# zx_kit2.net
KiCad netlist of a schematic drawn in EAGLE
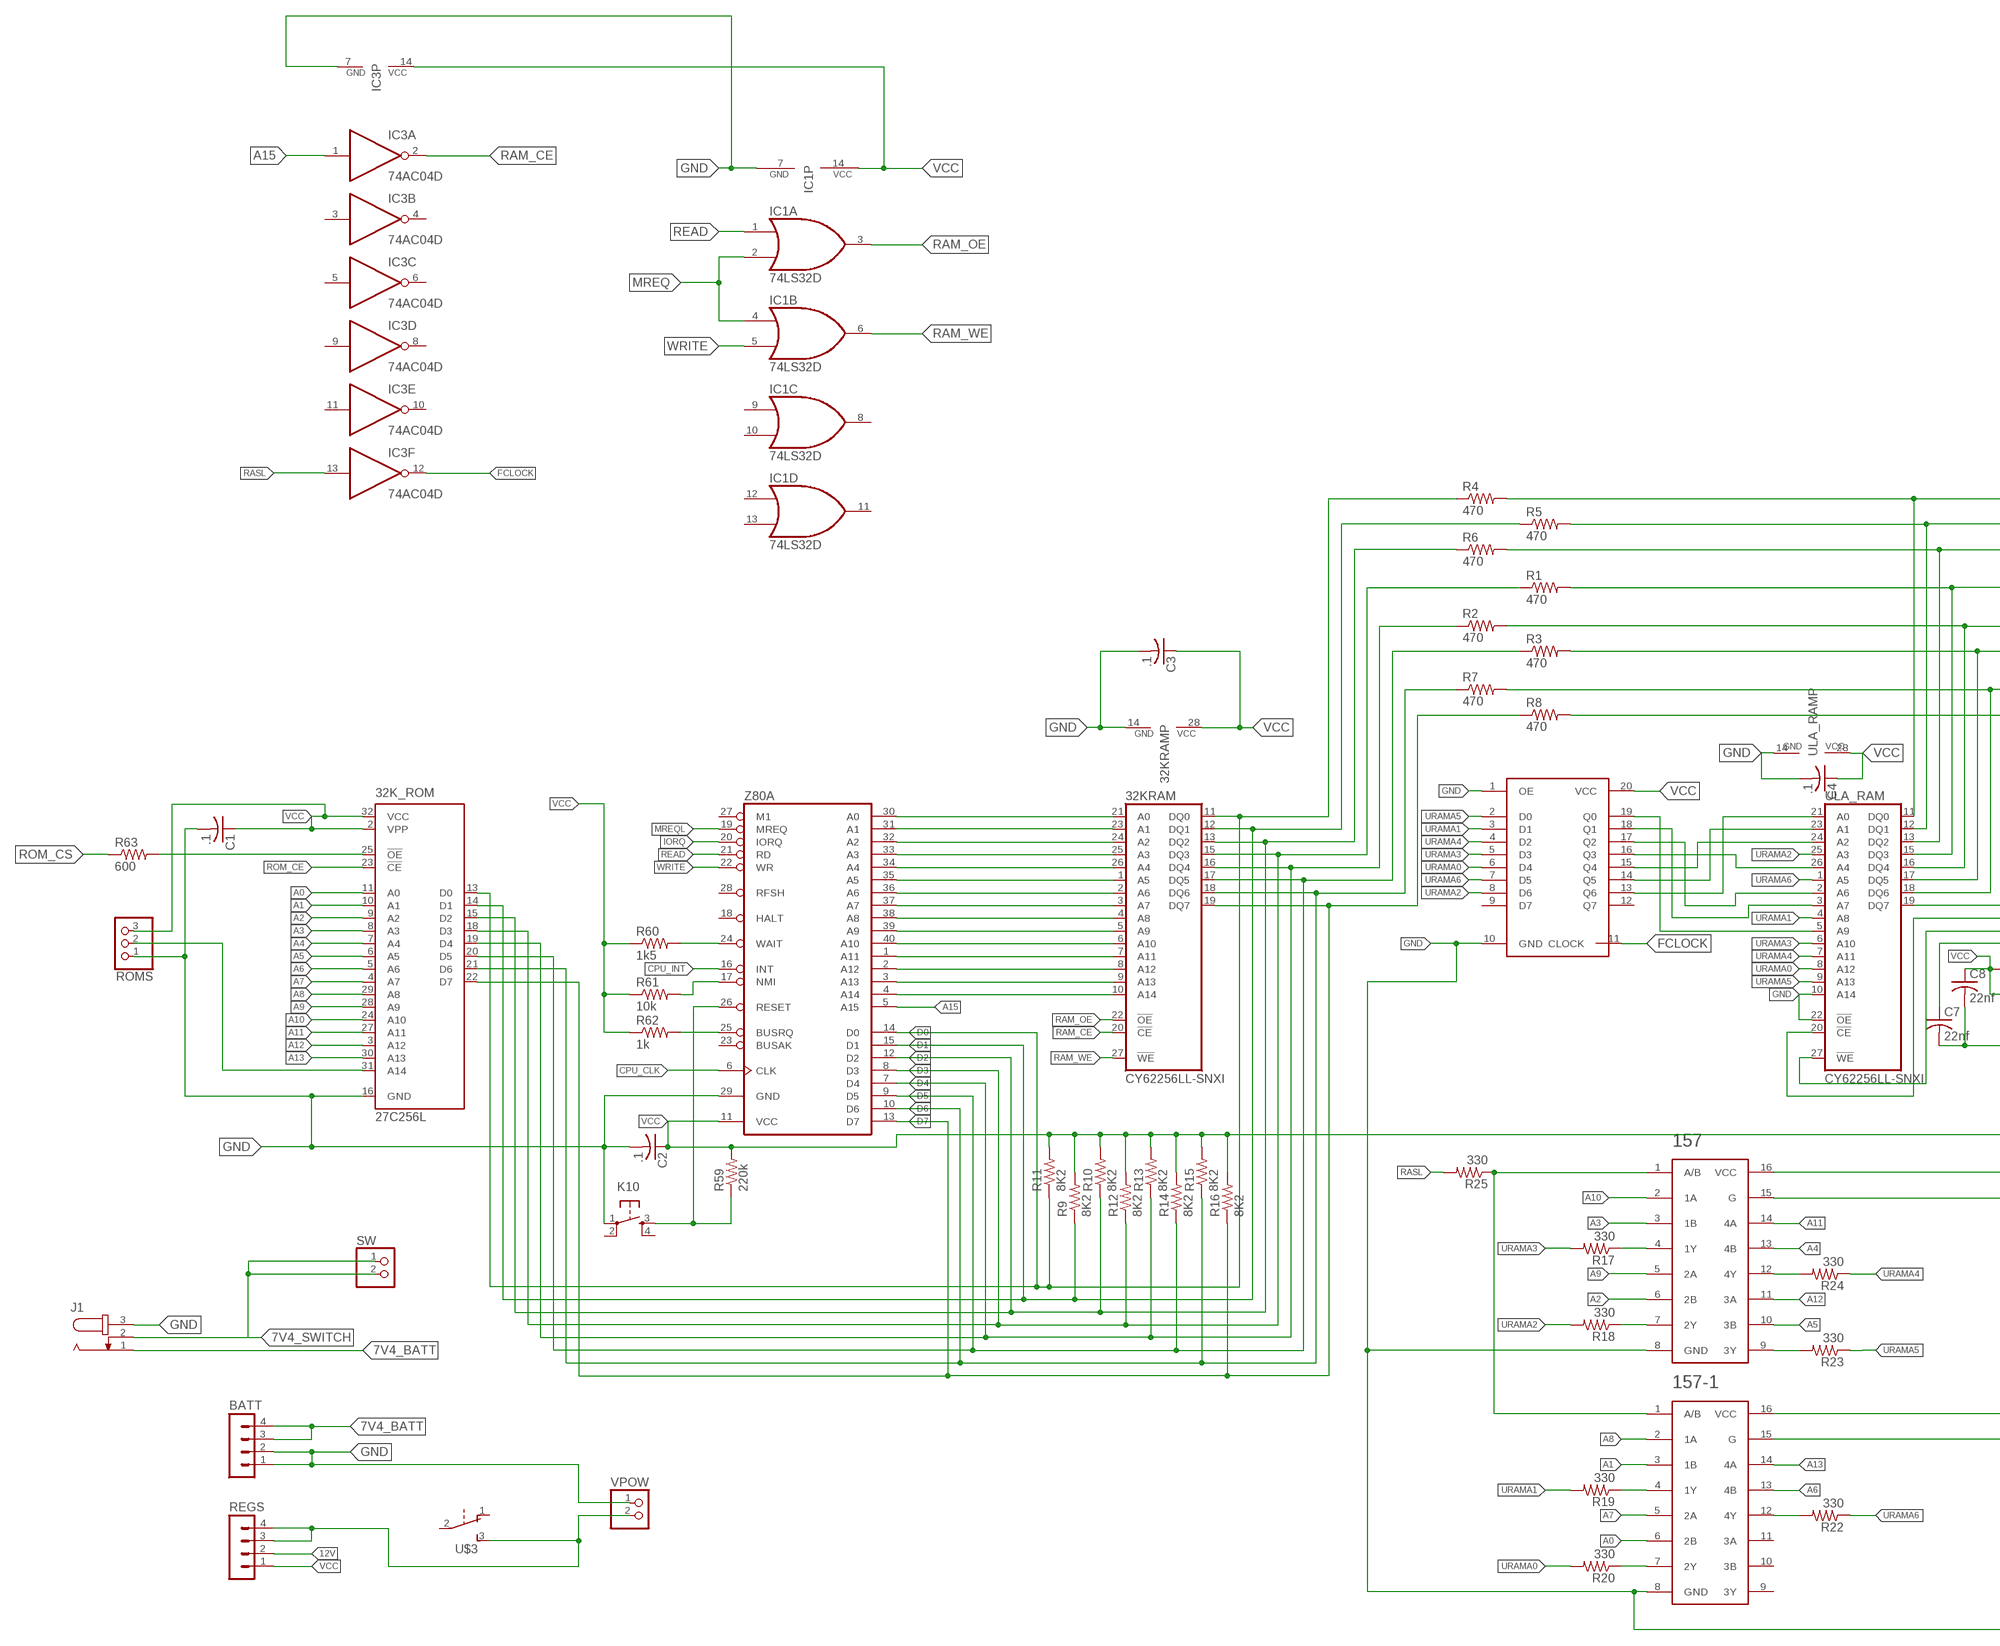
[diagram p0: schematic, sheet 1, part 1 of 3]
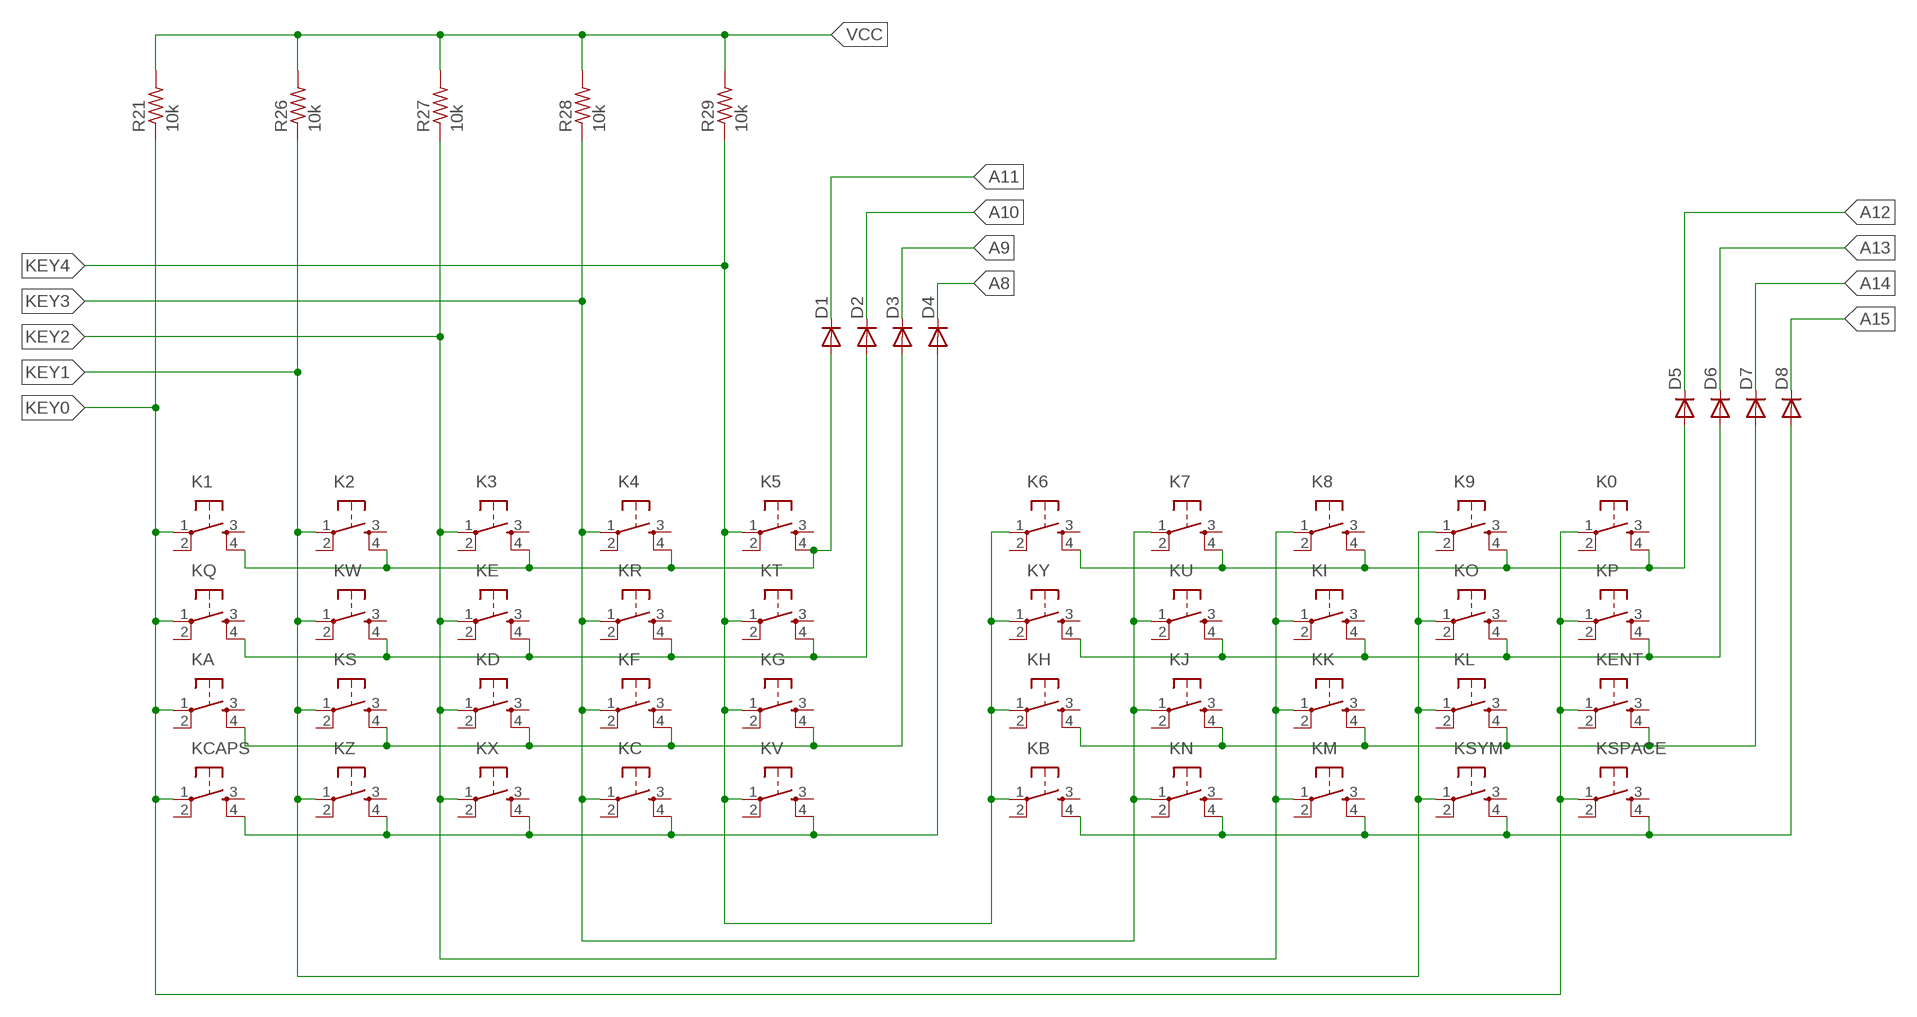
[diagram p1: schematic, sheet 1, part 2 of 3]
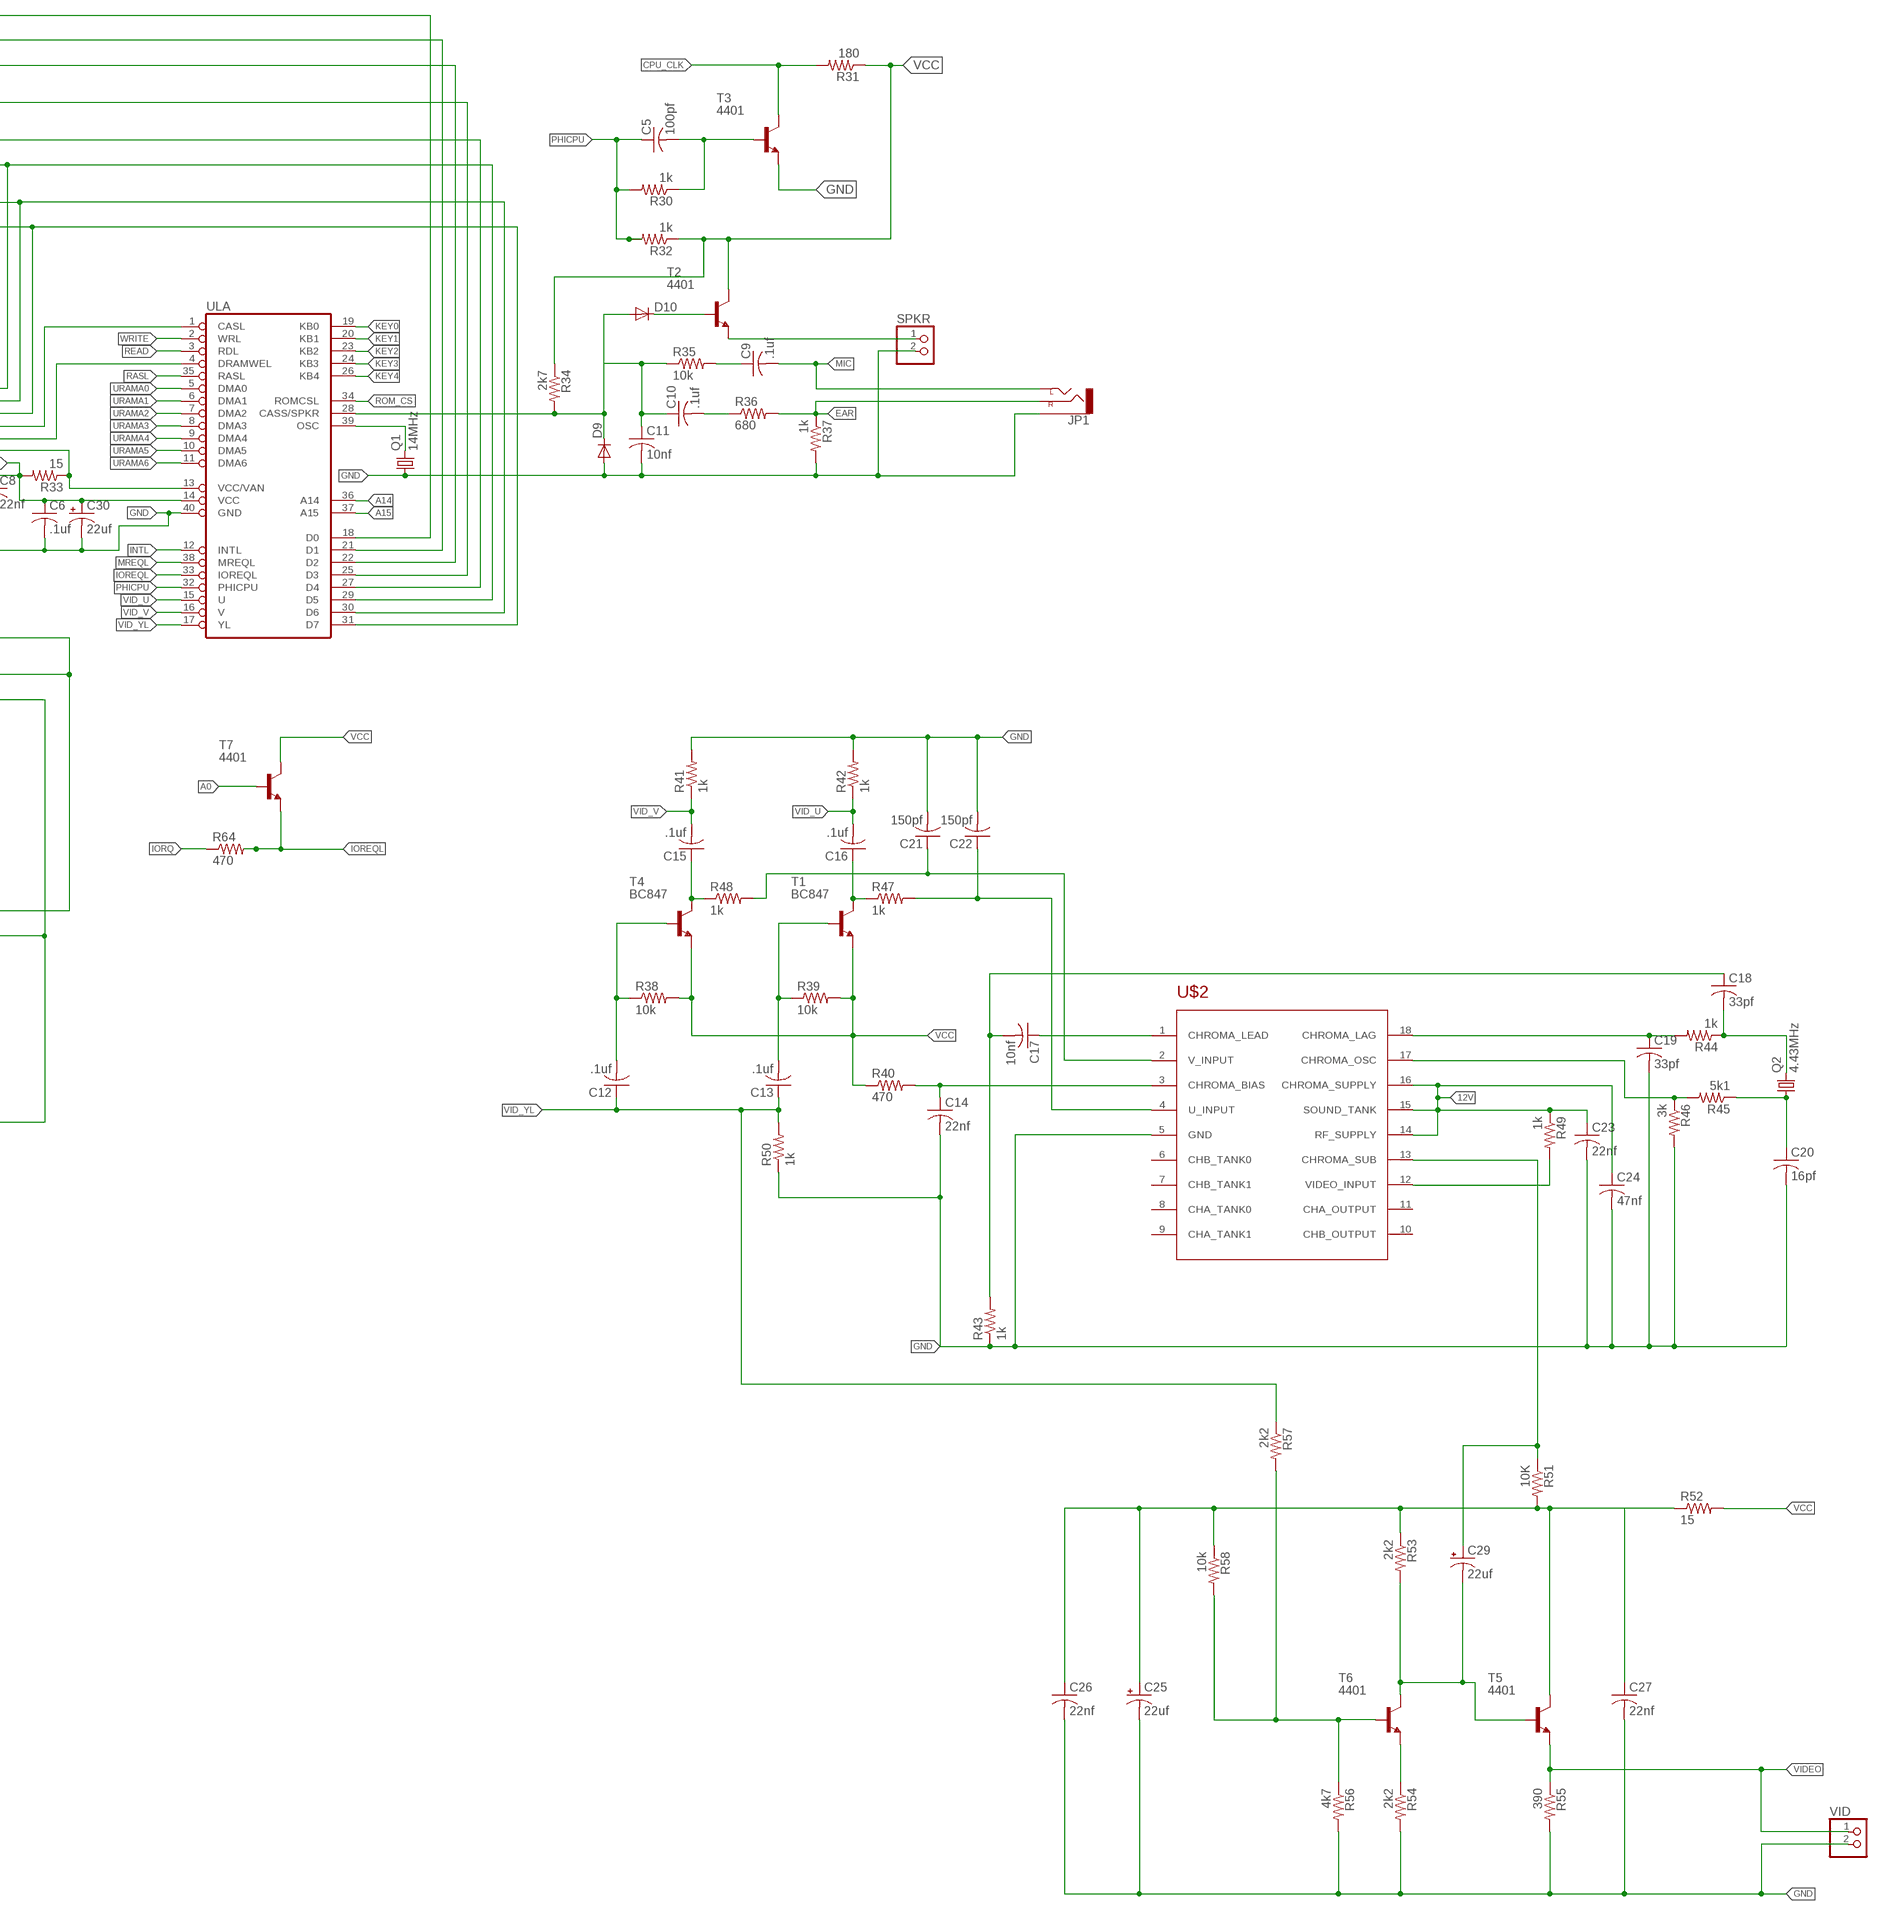
[diagram p2: schematic, sheet 1, part 3 of 3]

(export (version "E")
  (design (tool "Eeschema 10.0.6"))
  (components
    (comp (ref "32KRAM")
      (value "CY62256LL-SNXI")
      (footprint "eagle-import:SOJ28_3")
      (libsource (lib "eagle-import") (part "CY62256LL-?SNXI"))
    )
    (comp (ref "32K_ROM")
      (value "27C256L")
      (footprint "eagle-import:PLCC-32")
      (fields (field (name "MPN") "AT27C256R-70JU"))
      (libsource (lib "eagle-import") (part "27256LC"))
    )
    (comp (ref "157")
      (value "SN74HC157D")
      (footprint "eagle-import:SO16")
      (libsource (lib "eagle-import") (part "SN74HC157D"))
    )
    (comp (ref "157-1")
      (value "SN74HC157D")
      (footprint "eagle-import:SO16")
      (libsource (lib "eagle-import") (part "SN74HC157D"))
    )
    (comp (ref "BATT")
      (value "MA04-1")
      (footprint "eagle-import:MA04-1")
      (libsource (lib "eagle-import") (part "MA04-1"))
    )
    (comp (ref "C1")
      (value ".1")
      (footprint "eagle-import:C0805")
      (libsource (lib "eagle-import") (part "resistor_C-USC0805"))
    )
    (comp (ref "C2")
      (value ".1")
      (footprint "eagle-import:C0805")
      (libsource (lib "eagle-import") (part "resistor_C-USC0805"))
    )
    (comp (ref "C3")
      (value ".1")
      (footprint "eagle-import:C0805")
      (libsource (lib "eagle-import") (part "resistor_C-USC0805"))
    )
    (comp (ref "C4")
      (value ".1")
      (footprint "eagle-import:C0805")
      (libsource (lib "eagle-import") (part "resistor_C-USC0805"))
    )
    (comp (ref "C5")
      (value "100pf")
      (footprint "eagle-import:C0805")
      (libsource (lib "eagle-import") (part "C-USC0805"))
    )
    (comp (ref "C6")
      (value ".1uf")
      (footprint "eagle-import:C0805")
      (libsource (lib "eagle-import") (part "C-USC0805"))
    )
    (comp (ref "C7")
      (value "22nf")
      (footprint "eagle-import:C0805")
      (libsource (lib "eagle-import") (part "C-USC0805"))
    )
    (comp (ref "C8")
      (value "22nf")
      (footprint "eagle-import:C0805")
      (libsource (lib "eagle-import") (part "C-USC0805"))
    )
    (comp (ref "C9")
      (value ".1uf")
      (footprint "eagle-import:C0805")
      (libsource (lib "eagle-import") (part "C-USC0805"))
    )
    (comp (ref "C10")
      (value ".1uf")
      (footprint "eagle-import:C0805")
      (libsource (lib "eagle-import") (part "C-USC0805"))
    )
    (comp (ref "C11")
      (value "10nf")
      (footprint "eagle-import:C0805")
      (libsource (lib "eagle-import") (part "C-USC0805"))
    )
    (comp (ref "C12")
      (value ".1uf")
      (footprint "eagle-import:C0805")
      (libsource (lib "eagle-import") (part "C-USC0805"))
    )
    (comp (ref "C13")
      (value ".1uf")
      (footprint "eagle-import:C0805")
      (libsource (lib "eagle-import") (part "C-USC0805"))
    )
    (comp (ref "C14")
      (value "22nf")
      (footprint "eagle-import:C0805")
      (libsource (lib "eagle-import") (part "C-USC0805"))
    )
    (comp (ref "C15")
      (value ".1uf")
      (footprint "eagle-import:C0805")
      (libsource (lib "eagle-import") (part "C-USC0805"))
    )
    (comp (ref "C16")
      (value ".1uf")
      (footprint "eagle-import:C0805")
      (libsource (lib "eagle-import") (part "C-USC0805"))
    )
    (comp (ref "C17")
      (value "10nf")
      (footprint "eagle-import:C0805")
      (libsource (lib "eagle-import") (part "C-USC0805"))
    )
    (comp (ref "C18")
      (value "33pf")
      (footprint "eagle-import:C0805")
      (libsource (lib "eagle-import") (part "C-USC0805"))
    )
    (comp (ref "C19")
      (value "33pf")
      (footprint "eagle-import:C0805")
      (libsource (lib "eagle-import") (part "C-USC0805"))
    )
    (comp (ref "C20")
      (value "16pf")
      (footprint "eagle-import:C0805")
      (libsource (lib "eagle-import") (part "C-USC0805"))
    )
    (comp (ref "C21")
      (value "150pf")
      (footprint "eagle-import:C0805")
      (libsource (lib "eagle-import") (part "C-USC0805"))
    )
    (comp (ref "C22")
      (value "150pf")
      (footprint "eagle-import:C0805")
      (libsource (lib "eagle-import") (part "C-USC0805"))
    )
    (comp (ref "C23")
      (value "22nf")
      (footprint "eagle-import:C0805")
      (libsource (lib "eagle-import") (part "C-USC0805"))
    )
    (comp (ref "C24")
      (value "47nf")
      (footprint "eagle-import:C0805")
      (libsource (lib "eagle-import") (part "C-USC0805"))
    )
    (comp (ref "C25")
      (value "22uf")
      (footprint "eagle-import:PANASONIC_B")
      (libsource (lib "eagle-import") (part "CPOL-USB"))
    )
    (comp (ref "C26")
      (value "22nf")
      (footprint "eagle-import:C0805")
      (libsource (lib "eagle-import") (part "C-USC0805"))
    )
    (comp (ref "C27")
      (value "22nf")
      (footprint "eagle-import:C0805")
      (libsource (lib "eagle-import") (part "C-USC0805"))
    )
    (comp (ref "C29")
      (value "22uf")
      (footprint "eagle-import:PANASONIC_B")
      (libsource (lib "eagle-import") (part "CPOL-USB"))
    )
    (comp (ref "C30")
      (value "22uf")
      (footprint "eagle-import:PANASONIC_B")
      (libsource (lib "eagle-import") (part "CPOL-USB"))
    )
    (comp (ref "D1")
      (value "DIODE-SOD123")
      (footprint "eagle-import:SOD123")
      (libsource (lib "eagle-import") (part "DIODE-SOD123"))
    )
    (comp (ref "D2")
      (value "DIODE-SOD123")
      (footprint "eagle-import:SOD123")
      (libsource (lib "eagle-import") (part "DIODE-SOD123"))
    )
    (comp (ref "D3")
      (value "DIODE-SOD123")
      (footprint "eagle-import:SOD123")
      (libsource (lib "eagle-import") (part "DIODE-SOD123"))
    )
    (comp (ref "D4")
      (value "DIODE-SOD123")
      (footprint "eagle-import:SOD123")
      (libsource (lib "eagle-import") (part "DIODE-SOD123"))
    )
    (comp (ref "D5")
      (value "DIODE-SOD123")
      (footprint "eagle-import:SOD123")
      (libsource (lib "eagle-import") (part "DIODE-SOD123"))
    )
    (comp (ref "D6")
      (value "DIODE-SOD123")
      (footprint "eagle-import:SOD123")
      (libsource (lib "eagle-import") (part "DIODE-SOD123"))
    )
    (comp (ref "D7")
      (value "DIODE-SOD123")
      (footprint "eagle-import:SOD123")
      (libsource (lib "eagle-import") (part "DIODE-SOD123"))
    )
    (comp (ref "D8")
      (value "DIODE-SOD123")
      (footprint "eagle-import:SOD123")
      (libsource (lib "eagle-import") (part "DIODE-SOD123"))
    )
    (comp (ref "D9")
      (value "DIODE-SOD123")
      (footprint "eagle-import:SOD123")
      (libsource (lib "eagle-import") (part "DIODE-SOD123"))
    )
    (comp (ref "D10")
      (value "DIODE-SOD123")
      (footprint "eagle-import:SOD123")
      (libsource (lib "eagle-import") (part "DIODE-SOD123"))
    )
    (comp (ref "IC1")
      (value "74LS32D")
      (footprint "eagle-import:SO14")
      (libsource (lib "eagle-import") (part "7432DLS"))
    )
    (comp (ref "IC3")
      (value "74AC04D")
      (footprint "eagle-import:SO14")
      (libsource (lib "eagle-import") (part "7404DAC"))
    )
    (comp (ref "J1")
      (value "JACK-PLUG0")
      (footprint "eagle-import:SPC4077")
      (libsource (lib "eagle-import") (part "JACK-PLUG0"))
    )
    (comp (ref "JP1")
      (value "AUDIO-JACKPTH")
      (footprint "eagle-import:AUDIO-JACK")
      (libsource (lib "eagle-import") (part "AUDIO-JACKPTH"))
    )
    (comp (ref "K0")
      (value "DTS-6")
      (footprint "eagle-import:DTS-6")
      (libsource (lib "eagle-import") (part "DTS-6"))
    )
    (comp (ref "K1")
      (value "DTS-6")
      (footprint "eagle-import:DTS-6")
      (libsource (lib "eagle-import") (part "DTS-6"))
    )
    (comp (ref "K2")
      (value "DTS-6")
      (footprint "eagle-import:DTS-6")
      (libsource (lib "eagle-import") (part "DTS-6"))
    )
    (comp (ref "K3")
      (value "DTS-6")
      (footprint "eagle-import:DTS-6")
      (libsource (lib "eagle-import") (part "DTS-6"))
    )
    (comp (ref "K4")
      (value "DTS-6")
      (footprint "eagle-import:DTS-6")
      (libsource (lib "eagle-import") (part "DTS-6"))
    )
    (comp (ref "K5")
      (value "DTS-6")
      (footprint "eagle-import:DTS-6")
      (libsource (lib "eagle-import") (part "DTS-6"))
    )
    (comp (ref "K6")
      (value "DTS-6")
      (footprint "eagle-import:DTS-6")
      (libsource (lib "eagle-import") (part "DTS-6"))
    )
    (comp (ref "K7")
      (value "DTS-6")
      (footprint "eagle-import:DTS-6")
      (libsource (lib "eagle-import") (part "DTS-6"))
    )
    (comp (ref "K8")
      (value "DTS-6")
      (footprint "eagle-import:DTS-6")
      (libsource (lib "eagle-import") (part "DTS-6"))
    )
    (comp (ref "K9")
      (value "DTS-6")
      (footprint "eagle-import:DTS-6")
      (libsource (lib "eagle-import") (part "DTS-6"))
    )
    (comp (ref "K10")
      (value "DTS-6")
      (footprint "eagle-import:DTS-6")
      (libsource (lib "eagle-import") (part "DTS-6"))
    )
    (comp (ref "KA")
      (value "DTS-6")
      (footprint "eagle-import:DTS-6")
      (libsource (lib "eagle-import") (part "DTS-6"))
    )
    (comp (ref "KB")
      (value "DTS-6")
      (footprint "eagle-import:DTS-6")
      (libsource (lib "eagle-import") (part "DTS-6"))
    )
    (comp (ref "KC")
      (value "DTS-6")
      (footprint "eagle-import:DTS-6")
      (libsource (lib "eagle-import") (part "DTS-6"))
    )
    (comp (ref "KCAPS")
      (value "DTS-6")
      (footprint "eagle-import:DTS-6")
      (libsource (lib "eagle-import") (part "DTS-6"))
    )
    (comp (ref "KD")
      (value "DTS-6")
      (footprint "eagle-import:DTS-6")
      (libsource (lib "eagle-import") (part "DTS-6"))
    )
    (comp (ref "KE")
      (value "DTS-6")
      (footprint "eagle-import:DTS-6")
      (libsource (lib "eagle-import") (part "DTS-6"))
    )
    (comp (ref "KENT")
      (value "DTS-6")
      (footprint "eagle-import:DTS-6")
      (libsource (lib "eagle-import") (part "DTS-6"))
    )
    (comp (ref "KF")
      (value "DTS-6")
      (footprint "eagle-import:DTS-6")
      (libsource (lib "eagle-import") (part "DTS-6"))
    )
    (comp (ref "KG")
      (value "DTS-6")
      (footprint "eagle-import:DTS-6")
      (libsource (lib "eagle-import") (part "DTS-6"))
    )
    (comp (ref "KH")
      (value "DTS-6")
      (footprint "eagle-import:DTS-6")
      (libsource (lib "eagle-import") (part "DTS-6"))
    )
    (comp (ref "KI")
      (value "DTS-6")
      (footprint "eagle-import:DTS-6")
      (libsource (lib "eagle-import") (part "DTS-6"))
    )
    (comp (ref "KJ")
      (value "DTS-6")
      (footprint "eagle-import:DTS-6")
      (libsource (lib "eagle-import") (part "DTS-6"))
    )
    (comp (ref "KK")
      (value "DTS-6")
      (footprint "eagle-import:DTS-6")
      (libsource (lib "eagle-import") (part "DTS-6"))
    )
    (comp (ref "KL")
      (value "DTS-6")
      (footprint "eagle-import:DTS-6")
      (libsource (lib "eagle-import") (part "DTS-6"))
    )
    (comp (ref "KM")
      (value "DTS-6")
      (footprint "eagle-import:DTS-6")
      (libsource (lib "eagle-import") (part "DTS-6"))
    )
    (comp (ref "KN")
      (value "DTS-6")
      (footprint "eagle-import:DTS-6")
      (libsource (lib "eagle-import") (part "DTS-6"))
    )
    (comp (ref "KO")
      (value "DTS-6")
      (footprint "eagle-import:DTS-6")
      (libsource (lib "eagle-import") (part "DTS-6"))
    )
    (comp (ref "KP")
      (value "DTS-6")
      (footprint "eagle-import:DTS-6")
      (libsource (lib "eagle-import") (part "DTS-6"))
    )
    (comp (ref "KQ")
      (value "DTS-6")
      (footprint "eagle-import:DTS-6")
      (libsource (lib "eagle-import") (part "DTS-6"))
    )
    (comp (ref "KR")
      (value "DTS-6")
      (footprint "eagle-import:DTS-6")
      (libsource (lib "eagle-import") (part "DTS-6"))
    )
    (comp (ref "KS")
      (value "DTS-6")
      (footprint "eagle-import:DTS-6")
      (libsource (lib "eagle-import") (part "DTS-6"))
    )
    (comp (ref "KSPACE")
      (value "DTS-6")
      (footprint "eagle-import:DTS-6")
      (libsource (lib "eagle-import") (part "DTS-6"))
    )
    (comp (ref "KSYM")
      (value "DTS-6")
      (footprint "eagle-import:DTS-6")
      (libsource (lib "eagle-import") (part "DTS-6"))
    )
    (comp (ref "KT")
      (value "DTS-6")
      (footprint "eagle-import:DTS-6")
      (libsource (lib "eagle-import") (part "DTS-6"))
    )
    (comp (ref "KU")
      (value "DTS-6")
      (footprint "eagle-import:DTS-6")
      (libsource (lib "eagle-import") (part "DTS-6"))
    )
    (comp (ref "KV")
      (value "DTS-6")
      (footprint "eagle-import:DTS-6")
      (libsource (lib "eagle-import") (part "DTS-6"))
    )
    (comp (ref "KW")
      (value "DTS-6")
      (footprint "eagle-import:DTS-6")
      (libsource (lib "eagle-import") (part "DTS-6"))
    )
    (comp (ref "KX")
      (value "DTS-6")
      (footprint "eagle-import:DTS-6")
      (libsource (lib "eagle-import") (part "DTS-6"))
    )
    (comp (ref "KY")
      (value "DTS-6")
      (footprint "eagle-import:DTS-6")
      (libsource (lib "eagle-import") (part "DTS-6"))
    )
    (comp (ref "KZ")
      (value "DTS-6")
      (footprint "eagle-import:DTS-6")
      (libsource (lib "eagle-import") (part "DTS-6"))
    )
    (comp (ref "Q1")
      (value "14MHz")
      (footprint "eagle-import:CTS406")
      (libsource (lib "eagle-import") (part "CRYSTALCTS406"))
    )
    (comp (ref "Q2")
      (value "4.43MHz")
      (footprint "eagle-import:HC49_S")
      (libsource (lib "eagle-import") (part "CRYSTALHC49S"))
    )
    (comp (ref "R1")
      (value "470")
      (footprint "eagle-import:M0805")
      (libsource (lib "eagle-import") (part "R-US_M0805"))
    )
    (comp (ref "R2")
      (value "470")
      (footprint "eagle-import:M0805")
      (libsource (lib "eagle-import") (part "R-US_M0805"))
    )
    (comp (ref "R3")
      (value "470")
      (footprint "eagle-import:M0805")
      (libsource (lib "eagle-import") (part "R-US_M0805"))
    )
    (comp (ref "R4")
      (value "470")
      (footprint "eagle-import:M0805")
      (libsource (lib "eagle-import") (part "R-US_M0805"))
    )
    (comp (ref "R5")
      (value "470")
      (footprint "eagle-import:M0805")
      (libsource (lib "eagle-import") (part "R-US_M0805"))
    )
    (comp (ref "R6")
      (value "470")
      (footprint "eagle-import:M0805")
      (libsource (lib "eagle-import") (part "R-US_M0805"))
    )
    (comp (ref "R7")
      (value "470")
      (footprint "eagle-import:M0805")
      (libsource (lib "eagle-import") (part "R-US_M0805"))
    )
    (comp (ref "R8")
      (value "470")
      (footprint "eagle-import:M0805")
      (libsource (lib "eagle-import") (part "R-US_M0805"))
    )
    (comp (ref "R9")
      (value "8K2")
      (footprint "eagle-import:M0805")
      (libsource (lib "eagle-import") (part "R-US_M0805"))
    )
    (comp (ref "R10")
      (value "8K2")
      (footprint "eagle-import:M0805")
      (libsource (lib "eagle-import") (part "R-US_M0805"))
    )
    (comp (ref "R11")
      (value "8K2")
      (footprint "eagle-import:M0805")
      (libsource (lib "eagle-import") (part "R-US_M0805"))
    )
    (comp (ref "R12")
      (value "8K2")
      (footprint "eagle-import:M0805")
      (libsource (lib "eagle-import") (part "R-US_M0805"))
    )
    (comp (ref "R13")
      (value "8K2")
      (footprint "eagle-import:M0805")
      (libsource (lib "eagle-import") (part "R-US_M0805"))
    )
    (comp (ref "R14")
      (value "8K2")
      (footprint "eagle-import:M0805")
      (libsource (lib "eagle-import") (part "R-US_M0805"))
    )
    (comp (ref "R15")
      (value "8K2")
      (footprint "eagle-import:M0805")
      (libsource (lib "eagle-import") (part "R-US_M0805"))
    )
    (comp (ref "R16")
      (value "8K2")
      (footprint "eagle-import:M0805")
      (libsource (lib "eagle-import") (part "R-US_M0805"))
    )
    (comp (ref "R17")
      (value "330")
      (footprint "eagle-import:M0805")
      (libsource (lib "eagle-import") (part "R-US_M0805"))
    )
    (comp (ref "R18")
      (value "330")
      (footprint "eagle-import:M0805")
      (libsource (lib "eagle-import") (part "R-US_M0805"))
    )
    (comp (ref "R19")
      (value "330")
      (footprint "eagle-import:M0805")
      (libsource (lib "eagle-import") (part "R-US_M0805"))
    )
    (comp (ref "R20")
      (value "330")
      (footprint "eagle-import:M0805")
      (libsource (lib "eagle-import") (part "R-US_M0805"))
    )
    (comp (ref "R21")
      (value "10k")
      (footprint "eagle-import:R0805")
      (libsource (lib "eagle-import") (part "R-US_R0805"))
    )
    (comp (ref "R22")
      (value "330")
      (footprint "eagle-import:M0805")
      (libsource (lib "eagle-import") (part "R-US_M0805"))
    )
    (comp (ref "R23")
      (value "330")
      (footprint "eagle-import:M0805")
      (libsource (lib "eagle-import") (part "R-US_M0805"))
    )
    (comp (ref "R24")
      (value "330")
      (footprint "eagle-import:M0805")
      (libsource (lib "eagle-import") (part "R-US_M0805"))
    )
    (comp (ref "R25")
      (value "330")
      (footprint "eagle-import:M0805")
      (libsource (lib "eagle-import") (part "R-US_M0805"))
    )
    (comp (ref "R26")
      (value "10k")
      (footprint "eagle-import:R0805")
      (libsource (lib "eagle-import") (part "R-US_R0805"))
    )
    (comp (ref "R27")
      (value "10k")
      (footprint "eagle-import:R0805")
      (libsource (lib "eagle-import") (part "R-US_R0805"))
    )
    (comp (ref "R28")
      (value "10k")
      (footprint "eagle-import:R0805")
      (libsource (lib "eagle-import") (part "R-US_R0805"))
    )
    (comp (ref "R29")
      (value "10k")
      (footprint "eagle-import:R0805")
      (libsource (lib "eagle-import") (part "R-US_R0805"))
    )
    (comp (ref "R30")
      (value "1k")
      (footprint "eagle-import:R0805")
      (libsource (lib "eagle-import") (part "R-US_R0805"))
    )
    (comp (ref "R31")
      (value "180")
      (footprint "eagle-import:R0805")
      (libsource (lib "eagle-import") (part "R-US_R0805"))
    )
    (comp (ref "R32")
      (value "1k")
      (footprint "eagle-import:R0805")
      (libsource (lib "eagle-import") (part "R-US_R0805"))
    )
    (comp (ref "R33")
      (value "15")
      (footprint "eagle-import:R0805")
      (libsource (lib "eagle-import") (part "R-US_R0805"))
    )
    (comp (ref "R34")
      (value "2k7")
      (footprint "eagle-import:R0805")
      (libsource (lib "eagle-import") (part "R-US_R0805"))
    )
    (comp (ref "R35")
      (value "10k")
      (footprint "eagle-import:R0805")
      (libsource (lib "eagle-import") (part "R-US_R0805"))
    )
    (comp (ref "R36")
      (value "680")
      (footprint "eagle-import:R0805")
      (libsource (lib "eagle-import") (part "R-US_R0805"))
    )
    (comp (ref "R37")
      (value "1k")
      (footprint "eagle-import:R0805")
      (libsource (lib "eagle-import") (part "R-US_R0805"))
    )
    (comp (ref "R38")
      (value "10k")
      (footprint "eagle-import:R0805")
      (libsource (lib "eagle-import") (part "R-US_R0805"))
    )
    (comp (ref "R39")
      (value "10k")
      (footprint "eagle-import:R0805")
      (libsource (lib "eagle-import") (part "R-US_R0805"))
    )
    (comp (ref "R40")
      (value "470")
      (footprint "eagle-import:R0805")
      (libsource (lib "eagle-import") (part "R-US_R0805"))
    )
    (comp (ref "R41")
      (value "1k")
      (footprint "eagle-import:R0805")
      (libsource (lib "eagle-import") (part "R-US_R0805"))
    )
    (comp (ref "R42")
      (value "1k")
      (footprint "eagle-import:R0805")
      (libsource (lib "eagle-import") (part "R-US_R0805"))
    )
    (comp (ref "R43")
      (value "1k")
      (footprint "eagle-import:R0805")
      (libsource (lib "eagle-import") (part "R-US_R0805"))
    )
    (comp (ref "R44")
      (value "1k")
      (footprint "eagle-import:R0805")
      (libsource (lib "eagle-import") (part "R-US_R0805"))
    )
    (comp (ref "R45")
      (value "5k1")
      (footprint "eagle-import:R0805")
      (libsource (lib "eagle-import") (part "R-US_R0805"))
    )
    (comp (ref "R46")
      (value "3k")
      (footprint "eagle-import:R0805")
      (libsource (lib "eagle-import") (part "R-US_R0805"))
    )
    (comp (ref "R47")
      (value "1k")
      (footprint "eagle-import:R0805")
      (libsource (lib "eagle-import") (part "R-US_R0805"))
    )
    (comp (ref "R48")
      (value "1k")
      (footprint "eagle-import:R0805")
      (libsource (lib "eagle-import") (part "R-US_R0805"))
    )
    (comp (ref "R49")
      (value "1k")
      (footprint "eagle-import:R0805")
      (libsource (lib "eagle-import") (part "R-US_R0805"))
    )
    (comp (ref "R50")
      (value "1k")
      (footprint "eagle-import:R0805")
      (libsource (lib "eagle-import") (part "R-US_R0805"))
    )
    (comp (ref "R51")
      (value "10K")
      (footprint "eagle-import:R0805")
      (libsource (lib "eagle-import") (part "R-US_R0805"))
    )
    (comp (ref "R52")
      (value "15")
      (footprint "eagle-import:R0805")
      (libsource (lib "eagle-import") (part "R-US_R0805"))
    )
    (comp (ref "R53")
      (value "2k2")
      (footprint "eagle-import:R0805")
      (libsource (lib "eagle-import") (part "R-US_R0805"))
    )
    (comp (ref "R54")
      (value "2k2")
      (footprint "eagle-import:R0805")
      (libsource (lib "eagle-import") (part "R-US_R0805"))
    )
    (comp (ref "R55")
      (value "390")
      (footprint "eagle-import:R0805")
      (libsource (lib "eagle-import") (part "R-US_R0805"))
    )
    (comp (ref "R56")
      (value "4k7")
      (footprint "eagle-import:R0805")
      (libsource (lib "eagle-import") (part "R-US_R0805"))
    )
    (comp (ref "R57")
      (value "2k2")
      (footprint "eagle-import:R0805")
      (libsource (lib "eagle-import") (part "R-US_R0805"))
    )
    (comp (ref "R58")
      (value "10k")
      (footprint "eagle-import:R0805")
      (libsource (lib "eagle-import") (part "R-US_R0805"))
    )
    (comp (ref "R59")
      (value "220k")
      (footprint "eagle-import:M0805")
      (libsource (lib "eagle-import") (part "R-US_M0805"))
    )
    (comp (ref "R60")
      (value "1k5")
      (footprint "eagle-import:M0805")
      (libsource (lib "eagle-import") (part "R-US_M0805"))
    )
    (comp (ref "R61")
      (value "10k")
      (footprint "eagle-import:M0805")
      (libsource (lib "eagle-import") (part "R-US_M0805"))
    )
    (comp (ref "R62")
      (value "1k")
      (footprint "eagle-import:M0805")
      (libsource (lib "eagle-import") (part "R-US_M0805"))
    )
    (comp (ref "R63")
      (value "600")
      (footprint "eagle-import:M0805")
      (libsource (lib "eagle-import") (part "R-US_M0805"))
    )
    (comp (ref "R64")
      (value "470")
      (footprint "eagle-import:R0805")
      (libsource (lib "eagle-import") (part "R-US_R0805"))
    )
    (comp (ref "REGS")
      (value "MA04-1")
      (footprint "eagle-import:MA04-1")
      (libsource (lib "eagle-import") (part "MA04-1"))
    )
    (comp (ref "ROMS")
      (value "PINHD-1X3")
      (footprint "eagle-import:1X03")
      (libsource (lib "eagle-import") (part "PINHD-1X3"))
    )
    (comp (ref "SPKR")
      (value "PINHD-1X2")
      (footprint "eagle-import:1X02")
      (libsource (lib "eagle-import") (part "PINHD-1X2"))
    )
    (comp (ref "SW")
      (value "PINHD-1X2")
      (footprint "eagle-import:1X02")
      (libsource (lib "eagle-import") (part "PINHD-1X2"))
    )
    (comp (ref "T1")
      (value "BC847")
      (footprint "eagle-import:SOT23")
      (libsource (lib "eagle-import") (part "BC847"))
    )
    (comp (ref "T2")
      (value "4401")
      (footprint "eagle-import:SOT23-BEC")
      (libsource (lib "eagle-import") (part "-NPN-SOT23-BECMMBT4401LT1"))
    )
    (comp (ref "T3")
      (value "4401")
      (footprint "eagle-import:SOT23-BEC")
      (libsource (lib "eagle-import") (part "-NPN-SOT23-BECMMBT4401LT1"))
    )
    (comp (ref "T4")
      (value "BC847")
      (footprint "eagle-import:SOT23")
      (libsource (lib "eagle-import") (part "BC847"))
    )
    (comp (ref "T5")
      (value "4401")
      (footprint "eagle-import:SOT23-BEC")
      (libsource (lib "eagle-import") (part "-NPN-SOT23-BECMMBT4401LT1"))
    )
    (comp (ref "T6")
      (value "4401")
      (footprint "eagle-import:SOT23-BEC")
      (libsource (lib "eagle-import") (part "-NPN-SOT23-BECMMBT4401LT1"))
    )
    (comp (ref "T7")
      (value "4401")
      (footprint "eagle-import:SOT23-BEC")
      (libsource (lib "eagle-import") (part "-NPN-SOT23-BECMMBT4401LT1"))
    )
    (comp (ref "U$1")
      (value "MC74HC574A")
      (footprint "eagle-import:SO20W")
      (libsource (lib "eagle-import") (part "MC74HC574A"))
    )
    (comp (ref "U$2")
      (value "LM1889")
      (footprint "eagle-import:SOCKET-18")
      (libsource (lib "eagle-import") (part "LM1889"))
    )
    (comp (ref "U$3")
      (value "MS12ASW30_01")
      (footprint "eagle-import:MS12ASG30_01")
      (libsource (lib "eagle-import") (part "MS12ASW30_01"))
    )
    (comp (ref "ULA")
      (value "ZXULA")
      (footprint "eagle-import:DIL40")
      (libsource (lib "eagle-import") (part "ZXULA"))
    )
    (comp (ref "ULA_RAM")
      (value "CY62256LL-SNXI")
      (footprint "eagle-import:SOJ28_3")
      (libsource (lib "eagle-import") (part "CY62256LL-?SNXI"))
    )
    (comp (ref "VID")
      (value "PINHD-1X2")
      (footprint "eagle-import:1X02")
      (libsource (lib "eagle-import") (part "PINHD-1X2"))
    )
    (comp (ref "VPOW")
      (value "PINHD-1X2")
      (footprint "eagle-import:1X02")
      (libsource (lib "eagle-import") (part "PINHD-1X2"))
    )
    (comp (ref "Z80A")
      (value "Z80CPU")
      (footprint "eagle-import:DIL40")
      (libsource (lib "eagle-import") (part "Z80CPU"))
    )
  )
  (nets
    (net (code "1") (name "7V4_BATT") (class "Default")
      (node (ref "BATT") (pin "3") (pinfunction "3_3") (pintype "passive"))
      (node (ref "BATT") (pin "4") (pinfunction "4_4") (pintype "passive"))
      (node (ref "J1") (pin "1") (pinfunction "1_1") (pintype "passive"))
    )
    (net (code "2") (name "7V4_SWITCH") (class "Default")
      (node (ref "J1") (pin "2") (pinfunction "2_2") (pintype "passive"))
      (node (ref "SW") (pin "1") (pinfunction "1_1") (pintype "passive"))
      (node (ref "SW") (pin "2") (pinfunction "2_2") (pintype "passive"))
    )
    (net (code "3") (name "12V") (class "Default")
      (node (ref "C23") (pin "1") (pinfunction "1_1") (pintype "passive"))
      (node (ref "C24") (pin "1") (pinfunction "1_1") (pintype "passive"))
      (node (ref "R49") (pin "1") (pinfunction "1_1") (pintype "passive"))
      (node (ref "REGS") (pin "2") (pinfunction "2_2") (pintype "passive"))
      (node (ref "U$2") (pin "14") (pinfunction "RF_SUPPLY_14") (pintype "bidirectional"))
      (node (ref "U$2") (pin "15") (pinfunction "SOUND_TANK_15") (pintype "bidirectional"))
      (node (ref "U$2") (pin "16") (pinfunction "CHROMA_SUPPLY_16") (pintype "bidirectional"))
    )
    (net (code "4") (name "A0") (class "Default")
      (node (ref "157-1") (pin "6") (pinfunction "2B_6") (pintype "bidirectional"))
      (node (ref "32KRAM") (pin "21") (pinfunction "A0_21") (pintype "input"))
      (node (ref "32K_ROM") (pin "11") (pinfunction "A0_11") (pintype "input"))
      (node (ref "T7") (pin "B") (pinfunction "B_B") (pintype "passive"))
      (node (ref "Z80A") (pin "30") (pinfunction "A0_30") (pintype "output"))
    )
    (net (code "5") (name "A1") (class "Default")
      (node (ref "157-1") (pin "3") (pinfunction "1B_3") (pintype "bidirectional"))
      (node (ref "32KRAM") (pin "23") (pinfunction "A1_23") (pintype "input"))
      (node (ref "32K_ROM") (pin "10") (pinfunction "A1_10") (pintype "input"))
      (node (ref "Z80A") (pin "31") (pinfunction "A1_31") (pintype "output"))
    )
    (net (code "6") (name "A2") (class "Default")
      (node (ref "157") (pin "6") (pinfunction "2B_6") (pintype "bidirectional"))
      (node (ref "32KRAM") (pin "24") (pinfunction "A2_24") (pintype "input"))
      (node (ref "32K_ROM") (pin "9") (pinfunction "A2_9") (pintype "input"))
      (node (ref "Z80A") (pin "32") (pinfunction "A2_32") (pintype "output"))
    )
    (net (code "7") (name "A3") (class "Default")
      (node (ref "157") (pin "3") (pinfunction "1B_3") (pintype "bidirectional"))
      (node (ref "32KRAM") (pin "25") (pinfunction "A3_25") (pintype "input"))
      (node (ref "32K_ROM") (pin "8") (pinfunction "A3_8") (pintype "input"))
      (node (ref "Z80A") (pin "33") (pinfunction "A3_33") (pintype "output"))
    )
    (net (code "8") (name "A4") (class "Default")
      (node (ref "157") (pin "13") (pinfunction "4B_13") (pintype "bidirectional"))
      (node (ref "32KRAM") (pin "26") (pinfunction "A4_26") (pintype "input"))
      (node (ref "32K_ROM") (pin "7") (pinfunction "A4_7") (pintype "input"))
      (node (ref "Z80A") (pin "34") (pinfunction "A4_34") (pintype "output"))
    )
    (net (code "9") (name "A5") (class "Default")
      (node (ref "157") (pin "10") (pinfunction "3B_10") (pintype "bidirectional"))
      (node (ref "32KRAM") (pin "1") (pinfunction "A5_1") (pintype "input"))
      (node (ref "32K_ROM") (pin "6") (pinfunction "A5_6") (pintype "input"))
      (node (ref "Z80A") (pin "35") (pinfunction "A5_35") (pintype "output"))
    )
    (net (code "10") (name "A6") (class "Default")
      (node (ref "157-1") (pin "13") (pinfunction "4B_13") (pintype "bidirectional"))
      (node (ref "32KRAM") (pin "2") (pinfunction "A6_2") (pintype "input"))
      (node (ref "32K_ROM") (pin "5") (pinfunction "A6_5") (pintype "input"))
      (node (ref "Z80A") (pin "36") (pinfunction "A6_36") (pintype "output"))
    )
    (net (code "11") (name "A7") (class "Default")
      (node (ref "157-1") (pin "5") (pinfunction "2A_5") (pintype "bidirectional"))
      (node (ref "32KRAM") (pin "3") (pinfunction "A7_3") (pintype "input"))
      (node (ref "32K_ROM") (pin "4") (pinfunction "A7_4") (pintype "input"))
      (node (ref "Z80A") (pin "37") (pinfunction "A7_37") (pintype "output"))
    )
    (net (code "12") (name "A8") (class "Default")
      (node (ref "157-1") (pin "2") (pinfunction "1A_2") (pintype "bidirectional"))
      (node (ref "32KRAM") (pin "4") (pinfunction "A8_4") (pintype "input"))
      (node (ref "32K_ROM") (pin "29") (pinfunction "A8_29") (pintype "input"))
      (node (ref "D4") (pin "C") (pinfunction "C_C") (pintype "passive"))
      (node (ref "Z80A") (pin "38") (pinfunction "A8_38") (pintype "output"))
    )
    (net (code "13") (name "A9") (class "Default")
      (node (ref "157") (pin "5") (pinfunction "2A_5") (pintype "bidirectional"))
      (node (ref "32KRAM") (pin "5") (pinfunction "A9_5") (pintype "input"))
      (node (ref "32K_ROM") (pin "28") (pinfunction "A9_28") (pintype "input"))
      (node (ref "D3") (pin "C") (pinfunction "C_C") (pintype "passive"))
      (node (ref "Z80A") (pin "39") (pinfunction "A9_39") (pintype "output"))
    )
    (net (code "14") (name "A10") (class "Default")
      (node (ref "157") (pin "2") (pinfunction "1A_2") (pintype "bidirectional"))
      (node (ref "32KRAM") (pin "6") (pinfunction "A10_6") (pintype "input"))
      (node (ref "32K_ROM") (pin "24") (pinfunction "A10_24") (pintype "input"))
      (node (ref "D2") (pin "C") (pinfunction "C_C") (pintype "passive"))
      (node (ref "Z80A") (pin "40") (pinfunction "A10_40") (pintype "output"))
    )
    (net (code "15") (name "A11") (class "Default")
      (node (ref "157") (pin "14") (pinfunction "4A_14") (pintype "bidirectional"))
      (node (ref "32KRAM") (pin "7") (pinfunction "A11_7") (pintype "input"))
      (node (ref "32K_ROM") (pin "27") (pinfunction "A11_27") (pintype "input"))
      (node (ref "D1") (pin "C") (pinfunction "C_C") (pintype "passive"))
      (node (ref "Z80A") (pin "1") (pinfunction "A11_1") (pintype "output"))
    )
    (net (code "16") (name "A12") (class "Default")
      (node (ref "157") (pin "11") (pinfunction "3A_11") (pintype "bidirectional"))
      (node (ref "32KRAM") (pin "8") (pinfunction "A12_8") (pintype "input"))
      (node (ref "32K_ROM") (pin "3") (pinfunction "A12_3") (pintype "input"))
      (node (ref "D5") (pin "C") (pinfunction "C_C") (pintype "passive"))
      (node (ref "Z80A") (pin "2") (pinfunction "A12_2") (pintype "output"))
    )
    (net (code "17") (name "A13") (class "Default")
      (node (ref "157-1") (pin "14") (pinfunction "4A_14") (pintype "bidirectional"))
      (node (ref "32KRAM") (pin "9") (pinfunction "A13_9") (pintype "input"))
      (node (ref "32K_ROM") (pin "30") (pinfunction "A13_30") (pintype "input"))
      (node (ref "D6") (pin "C") (pinfunction "C_C") (pintype "passive"))
      (node (ref "Z80A") (pin "3") (pinfunction "A13_3") (pintype "output"))
    )
    (net (code "18") (name "A14") (class "Default")
      (node (ref "32KRAM") (pin "10") (pinfunction "A14_10") (pintype "input"))
      (node (ref "D7") (pin "C") (pinfunction "C_C") (pintype "passive"))
      (node (ref "ULA") (pin "36") (pinfunction "A14_36") (pintype "output"))
      (node (ref "Z80A") (pin "4") (pinfunction "A14_4") (pintype "output"))
    )
    (net (code "19") (name "A15") (class "Default")
      (node (ref "D8") (pin "C") (pinfunction "C_C") (pintype "passive"))
      (node (ref "IC3") (pin "1") (pinfunction "I_1") (pintype "input"))
      (node (ref "ULA") (pin "37") (pinfunction "A15_37") (pintype "output"))
      (node (ref "Z80A") (pin "5") (pinfunction "A15_5") (pintype "output"))
    )
    (net (code "20") (name "CPU_CLK") (class "Default")
      (node (ref "R31") (pin "2") (pinfunction "2_2") (pintype "passive"))
      (node (ref "T3") (pin "C") (pinfunction "C_C") (pintype "passive"))
      (node (ref "Z80A") (pin "6") (pinfunction "CLK_6") (pintype "input"))
    )
    (net (code "21") (name "CPU_INT") (class "Default")
      (node (ref "Z80A") (pin "16") (pinfunction "INT_16") (pintype "input"))
    )
    (net (code "22") (name "D0") (class "Default")
      (node (ref "32KRAM") (pin "11") (pinfunction "DQ0_11") (pintype "bidirectional"))
      (node (ref "32K_ROM") (pin "13") (pinfunction "D0_13") (pintype "tri_state"))
      (node (ref "R11") (pin "1") (pinfunction "1_1") (pintype "passive"))
      (node (ref "R4") (pin "1") (pinfunction "1_1") (pintype "passive"))
      (node (ref "Z80A") (pin "14") (pinfunction "D0_14") (pintype "bidirectional"))
    )
    (net (code "23") (name "D1") (class "Default")
      (node (ref "32KRAM") (pin "12") (pinfunction "DQ1_12") (pintype "bidirectional"))
      (node (ref "32K_ROM") (pin "14") (pinfunction "D1_14") (pintype "tri_state"))
      (node (ref "R5") (pin "1") (pinfunction "1_1") (pintype "passive"))
      (node (ref "R9") (pin "1") (pinfunction "1_1") (pintype "passive"))
      (node (ref "Z80A") (pin "15") (pinfunction "D1_15") (pintype "bidirectional"))
    )
    (net (code "24") (name "D2") (class "Default")
      (node (ref "32KRAM") (pin "13") (pinfunction "DQ2_13") (pintype "bidirectional"))
      (node (ref "32K_ROM") (pin "15") (pinfunction "D2_15") (pintype "tri_state"))
      (node (ref "R10") (pin "1") (pinfunction "1_1") (pintype "passive"))
      (node (ref "R6") (pin "1") (pinfunction "1_1") (pintype "passive"))
      (node (ref "Z80A") (pin "12") (pinfunction "D2_12") (pintype "bidirectional"))
    )
    (net (code "25") (name "D3") (class "Default")
      (node (ref "32KRAM") (pin "15") (pinfunction "DQ3_15") (pintype "bidirectional"))
      (node (ref "32K_ROM") (pin "18") (pinfunction "D3_18") (pintype "tri_state"))
      (node (ref "R1") (pin "1") (pinfunction "1_1") (pintype "passive"))
      (node (ref "R12") (pin "1") (pinfunction "1_1") (pintype "passive"))
      (node (ref "Z80A") (pin "8") (pinfunction "D3_8") (pintype "bidirectional"))
    )
    (net (code "26") (name "D4") (class "Default")
      (node (ref "32KRAM") (pin "16") (pinfunction "DQ4_16") (pintype "bidirectional"))
      (node (ref "32K_ROM") (pin "19") (pinfunction "D4_19") (pintype "tri_state"))
      (node (ref "R13") (pin "1") (pinfunction "1_1") (pintype "passive"))
      (node (ref "R2") (pin "1") (pinfunction "1_1") (pintype "passive"))
      (node (ref "Z80A") (pin "7") (pinfunction "D4_7") (pintype "bidirectional"))
    )
    (net (code "27") (name "D5") (class "Default")
      (node (ref "32KRAM") (pin "17") (pinfunction "DQ5_17") (pintype "bidirectional"))
      (node (ref "32K_ROM") (pin "20") (pinfunction "D5_20") (pintype "tri_state"))
      (node (ref "R14") (pin "1") (pinfunction "1_1") (pintype "passive"))
      (node (ref "R3") (pin "1") (pinfunction "1_1") (pintype "passive"))
      (node (ref "Z80A") (pin "9") (pinfunction "D5_9") (pintype "bidirectional"))
    )
    (net (code "28") (name "D6") (class "Default")
      (node (ref "32KRAM") (pin "18") (pinfunction "DQ6_18") (pintype "bidirectional"))
      (node (ref "32K_ROM") (pin "21") (pinfunction "D6_21") (pintype "tri_state"))
      (node (ref "R15") (pin "1") (pinfunction "1_1") (pintype "passive"))
      (node (ref "R7") (pin "1") (pinfunction "1_1") (pintype "passive"))
      (node (ref "Z80A") (pin "10") (pinfunction "D6_10") (pintype "bidirectional"))
    )
    (net (code "29") (name "D7") (class "Default")
      (node (ref "32KRAM") (pin "19") (pinfunction "DQ7_19") (pintype "bidirectional"))
      (node (ref "32K_ROM") (pin "22") (pinfunction "D7_22") (pintype "tri_state"))
      (node (ref "R16") (pin "1") (pinfunction "1_1") (pintype "passive"))
      (node (ref "R8") (pin "1") (pinfunction "1_1") (pintype "passive"))
      (node (ref "Z80A") (pin "13") (pinfunction "D7_13") (pintype "bidirectional"))
    )
    (net (code "30") (name "EAR") (class "Default")
      (node (ref "JP1") (pin "RING") (pinfunction "RIGHT_RING") (pintype "bidirectional"))
      (node (ref "R36") (pin "2") (pinfunction "2_2") (pintype "passive"))
      (node (ref "R37") (pin "1") (pinfunction "1_1") (pintype "passive"))
    )
    (net (code "31") (name "FCLOCK") (class "Default")
      (node (ref "IC3") (pin "12") (pinfunction "O_12") (pintype "output"))
      (node (ref "U$1") (pin "11") (pinfunction "CLOCK_11") (pintype "bidirectional"))
    )
    (net (code "32") (name "GND") (class "Default")
      (node (ref "157") (pin "15") (pinfunction "G_15") (pintype "bidirectional"))
      (node (ref "157") (pin "8") (pinfunction "GND_8") (pintype "bidirectional"))
      (node (ref "157-1") (pin "15") (pinfunction "G_15") (pintype "bidirectional"))
      (node (ref "157-1") (pin "8") (pinfunction "GND_8") (pintype "bidirectional"))
      (node (ref "32KRAM") (pin "14") (pinfunction "GND_14") (pintype "power_in"))
      (node (ref "32K_ROM") (pin "16") (pinfunction "GND_16") (pintype "power_in"))
      (node (ref "BATT") (pin "1") (pinfunction "1_1") (pintype "passive"))
      (node (ref "BATT") (pin "2") (pinfunction "2_2") (pintype "passive"))
      (node (ref "C1") (pin "2") (pinfunction "2_2") (pintype "passive"))
      (node (ref "C11") (pin "2") (pinfunction "2_2") (pintype "passive"))
      (node (ref "C14") (pin "2") (pinfunction "2_2") (pintype "passive"))
      (node (ref "C19") (pin "2") (pinfunction "2_2") (pintype "passive"))
      (node (ref "C2") (pin "2") (pinfunction "2_2") (pintype "passive"))
      (node (ref "C20") (pin "2") (pinfunction "2_2") (pintype "passive"))
      (node (ref "C21") (pin "2") (pinfunction "2_2") (pintype "passive"))
      (node (ref "C22") (pin "2") (pinfunction "2_2") (pintype "passive"))
      (node (ref "C23") (pin "2") (pinfunction "2_2") (pintype "passive"))
      (node (ref "C24") (pin "2") (pinfunction "2_2") (pintype "passive"))
      (node (ref "C25") (pin "-") (pinfunction "-_-") (pintype "passive"))
      (node (ref "C26") (pin "2") (pinfunction "2_2") (pintype "passive"))
      (node (ref "C27") (pin "2") (pinfunction "2_2") (pintype "passive"))
      (node (ref "C3") (pin "2") (pinfunction "2_2") (pintype "passive"))
      (node (ref "C30") (pin "-") (pinfunction "-_-") (pintype "passive"))
      (node (ref "C4") (pin "2") (pinfunction "2_2") (pintype "passive"))
      (node (ref "C6") (pin "2") (pinfunction "2_2") (pintype "passive"))
      (node (ref "C7") (pin "2") (pinfunction "2_2") (pintype "passive"))
      (node (ref "C8") (pin "2") (pinfunction "2_2") (pintype "passive"))
      (node (ref "D9") (pin "A") (pinfunction "A_A") (pintype "passive"))
      (node (ref "IC1") (pin "7") (pinfunction "GND_7") (pintype "power_in"))
      (node (ref "IC3") (pin "7") (pinfunction "GND_7") (pintype "power_in"))
      (node (ref "J1") (pin "3") (pinfunction "3_3") (pintype "passive"))
      (node (ref "JP1") (pin "SLEEVE") (pinfunction "SLEEVE_SLEEVE") (pintype "bidirectional"))
      (node (ref "K10") (pin "1") (pinfunction "1_1") (pintype "passive"))
      (node (ref "Q1") (pin "1") (pinfunction "1_1") (pintype "passive"))
      (node (ref "R37") (pin "2") (pinfunction "2_2") (pintype "passive"))
      (node (ref "R41") (pin "2") (pinfunction "2_2") (pintype "passive"))
      (node (ref "R42") (pin "2") (pinfunction "2_2") (pintype "passive"))
      (node (ref "R43") (pin "1") (pinfunction "1_1") (pintype "passive"))
      (node (ref "R46") (pin "2") (pinfunction "2_2") (pintype "passive"))
      (node (ref "R50") (pin "1") (pinfunction "1_1") (pintype "passive"))
      (node (ref "R54") (pin "2") (pinfunction "2_2") (pintype "passive"))
      (node (ref "R55") (pin "2") (pinfunction "2_2") (pintype "passive"))
      (node (ref "R56") (pin "2") (pinfunction "2_2") (pintype "passive"))
      (node (ref "ROMS") (pin "1") (pinfunction "1_1") (pintype "passive"))
      (node (ref "SPKR") (pin "2") (pinfunction "2_2") (pintype "passive"))
      (node (ref "T3") (pin "E") (pinfunction "E_E") (pintype "passive"))
      (node (ref "U$1") (pin "1") (pinfunction "OE_1") (pintype "bidirectional"))
      (node (ref "U$1") (pin "10") (pinfunction "GND_10") (pintype "bidirectional"))
      (node (ref "U$2") (pin "5") (pinfunction "GND_5") (pintype "bidirectional"))
      (node (ref "ULA") (pin "40") (pinfunction "GND_40") (pintype "output"))
      (node (ref "ULA_RAM") (pin "10") (pinfunction "A14_10") (pintype "input"))
      (node (ref "ULA_RAM") (pin "14") (pinfunction "GND_14") (pintype "power_in"))
      (node (ref "ULA_RAM") (pin "22") (pinfunction "~{OE}_22") (pintype "input"))
      (node (ref "VID") (pin "2") (pinfunction "2_2") (pintype "passive"))
      (node (ref "VPOW") (pin "1") (pinfunction "1_1") (pintype "passive"))
      (node (ref "Z80A") (pin "29") (pinfunction "GND_29") (pintype "power_in"))
    )
    (net (code "33") (name "INTL") (class "Default")
      (node (ref "ULA") (pin "12") (pinfunction "INTL_12") (pintype "input"))
    )
    (net (code "34") (name "IOREQL") (class "Default")
      (node (ref "R64") (pin "2") (pinfunction "2_2") (pintype "passive"))
      (node (ref "T7") (pin "E") (pinfunction "E_E") (pintype "passive"))
      (node (ref "ULA") (pin "33") (pinfunction "IOREQL_33") (pintype "output"))
    )
    (net (code "35") (name "IORQ") (class "Default")
      (node (ref "R64") (pin "1") (pinfunction "1_1") (pintype "passive"))
      (node (ref "Z80A") (pin "20") (pinfunction "IORQ_20") (pintype "output"))
    )
    (net (code "36") (name "KEY0") (class "Default")
      (node (ref "K0") (pin "1") (pinfunction "1_1") (pintype "passive"))
      (node (ref "K1") (pin "1") (pinfunction "1_1") (pintype "passive"))
      (node (ref "KA") (pin "1") (pinfunction "1_1") (pintype "passive"))
      (node (ref "KCAPS") (pin "1") (pinfunction "1_1") (pintype "passive"))
      (node (ref "KENT") (pin "1") (pinfunction "1_1") (pintype "passive"))
      (node (ref "KP") (pin "1") (pinfunction "1_1") (pintype "passive"))
      (node (ref "KQ") (pin "1") (pinfunction "1_1") (pintype "passive"))
      (node (ref "KSPACE") (pin "1") (pinfunction "1_1") (pintype "passive"))
      (node (ref "R21") (pin "1") (pinfunction "1_1") (pintype "passive"))
      (node (ref "ULA") (pin "19") (pinfunction "KB0_19") (pintype "output"))
    )
    (net (code "37") (name "KEY1") (class "Default")
      (node (ref "K2") (pin "1") (pinfunction "1_1") (pintype "passive"))
      (node (ref "K9") (pin "1") (pinfunction "1_1") (pintype "passive"))
      (node (ref "KL") (pin "1") (pinfunction "1_1") (pintype "passive"))
      (node (ref "KO") (pin "1") (pinfunction "1_1") (pintype "passive"))
      (node (ref "KS") (pin "1") (pinfunction "1_1") (pintype "passive"))
      (node (ref "KSYM") (pin "1") (pinfunction "1_1") (pintype "passive"))
      (node (ref "KW") (pin "1") (pinfunction "1_1") (pintype "passive"))
      (node (ref "KZ") (pin "1") (pinfunction "1_1") (pintype "passive"))
      (node (ref "R26") (pin "1") (pinfunction "1_1") (pintype "passive"))
      (node (ref "ULA") (pin "20") (pinfunction "KB1_20") (pintype "output"))
    )
    (net (code "38") (name "KEY2") (class "Default")
      (node (ref "K3") (pin "1") (pinfunction "1_1") (pintype "passive"))
      (node (ref "K8") (pin "1") (pinfunction "1_1") (pintype "passive"))
      (node (ref "KD") (pin "1") (pinfunction "1_1") (pintype "passive"))
      (node (ref "KE") (pin "1") (pinfunction "1_1") (pintype "passive"))
      (node (ref "KI") (pin "1") (pinfunction "1_1") (pintype "passive"))
      (node (ref "KK") (pin "1") (pinfunction "1_1") (pintype "passive"))
      (node (ref "KM") (pin "1") (pinfunction "1_1") (pintype "passive"))
      (node (ref "KX") (pin "1") (pinfunction "1_1") (pintype "passive"))
      (node (ref "R27") (pin "1") (pinfunction "1_1") (pintype "passive"))
      (node (ref "ULA") (pin "23") (pinfunction "KB2_23") (pintype "output"))
    )
    (net (code "39") (name "KEY3") (class "Default")
      (node (ref "K4") (pin "1") (pinfunction "1_1") (pintype "passive"))
      (node (ref "K7") (pin "1") (pinfunction "1_1") (pintype "passive"))
      (node (ref "KC") (pin "1") (pinfunction "1_1") (pintype "passive"))
      (node (ref "KF") (pin "1") (pinfunction "1_1") (pintype "passive"))
      (node (ref "KJ") (pin "1") (pinfunction "1_1") (pintype "passive"))
      (node (ref "KN") (pin "1") (pinfunction "1_1") (pintype "passive"))
      (node (ref "KR") (pin "1") (pinfunction "1_1") (pintype "passive"))
      (node (ref "KU") (pin "1") (pinfunction "1_1") (pintype "passive"))
      (node (ref "R28") (pin "1") (pinfunction "1_1") (pintype "passive"))
      (node (ref "ULA") (pin "24") (pinfunction "KB3_24") (pintype "output"))
    )
    (net (code "40") (name "KEY4") (class "Default")
      (node (ref "K5") (pin "1") (pinfunction "1_1") (pintype "passive"))
      (node (ref "K6") (pin "1") (pinfunction "1_1") (pintype "passive"))
      (node (ref "KB") (pin "1") (pinfunction "1_1") (pintype "passive"))
      (node (ref "KG") (pin "1") (pinfunction "1_1") (pintype "passive"))
      (node (ref "KH") (pin "1") (pinfunction "1_1") (pintype "passive"))
      (node (ref "KT") (pin "1") (pinfunction "1_1") (pintype "passive"))
      (node (ref "KV") (pin "1") (pinfunction "1_1") (pintype "passive"))
      (node (ref "KY") (pin "1") (pinfunction "1_1") (pintype "passive"))
      (node (ref "R29") (pin "1") (pinfunction "1_1") (pintype "passive"))
      (node (ref "ULA") (pin "26") (pinfunction "KB4_26") (pintype "output"))
    )
    (net (code "41") (name "MIC") (class "Default")
      (node (ref "C9") (pin "2") (pinfunction "2_2") (pintype "passive"))
      (node (ref "JP1") (pin "TIP") (pinfunction "LEFT_TIP") (pintype "bidirectional"))
    )
    (net (code "42") (name "MREQ") (class "Default")
      (node (ref "IC1") (pin "2") (pinfunction "I1_2") (pintype "input"))
      (node (ref "IC1") (pin "4") (pinfunction "I0_4") (pintype "input"))
    )
    (net (code "43") (name "MREQL") (class "Default")
      (node (ref "ULA") (pin "38") (pinfunction "MREQL_38") (pintype "output"))
      (node (ref "Z80A") (pin "19") (pinfunction "MREQ_19") (pintype "output"))
    )
    (net (code "44") (name "Net-(32K_ROM-A14)") (class "Default")
      (node (ref "32K_ROM") (pin "31") (pinfunction "A14_31") (pintype "input"))
      (node (ref "ROMS") (pin "2") (pinfunction "2_2") (pintype "passive"))
    )
    (net (code "45") (name "Net-(32K_ROM-~{OE})") (class "Default")
      (node (ref "32K_ROM") (pin "25") (pinfunction "~{OE}_25") (pintype "input"))
      (node (ref "R63") (pin "2") (pinfunction "2_2") (pintype "passive"))
    )
    (net (code "46") (name "Net-(157-1-1Y)") (class "Default")
      (node (ref "157-1") (pin "4") (pinfunction "1Y_4") (pintype "bidirectional"))
      (node (ref "R19") (pin "1") (pinfunction "1_1") (pintype "passive"))
    )
    (net (code "47") (name "Net-(157-1-2Y)") (class "Default")
      (node (ref "157-1") (pin "7") (pinfunction "2Y_7") (pintype "bidirectional"))
      (node (ref "R20") (pin "1") (pinfunction "1_1") (pintype "passive"))
    )
    (net (code "48") (name "Net-(157-1-4Y)") (class "Default")
      (node (ref "157-1") (pin "12") (pinfunction "4Y_12") (pintype "bidirectional"))
      (node (ref "R22") (pin "2") (pinfunction "2_2") (pintype "passive"))
    )
    (net (code "49") (name "Net-(157-1-A{slash}B)") (class "Default")
      (node (ref "157") (pin "1") (pinfunction "A/B_1") (pintype "bidirectional"))
      (node (ref "157-1") (pin "1") (pinfunction "A/B_1") (pintype "bidirectional"))
      (node (ref "R25") (pin "1") (pinfunction "1_1") (pintype "passive"))
    )
    (net (code "50") (name "Net-(157-1Y)") (class "Default")
      (node (ref "157") (pin "4") (pinfunction "1Y_4") (pintype "bidirectional"))
      (node (ref "R17") (pin "1") (pinfunction "1_1") (pintype "passive"))
    )
    (net (code "51") (name "Net-(157-2Y)") (class "Default")
      (node (ref "157") (pin "7") (pinfunction "2Y_7") (pintype "bidirectional"))
      (node (ref "R18") (pin "1") (pinfunction "1_1") (pintype "passive"))
    )
    (net (code "52") (name "Net-(157-3Y)") (class "Default")
      (node (ref "157") (pin "9") (pinfunction "3Y_9") (pintype "bidirectional"))
      (node (ref "R23") (pin "2") (pinfunction "2_2") (pintype "passive"))
    )
    (net (code "53") (name "Net-(157-4Y)") (class "Default")
      (node (ref "157") (pin "12") (pinfunction "4Y_12") (pintype "bidirectional"))
      (node (ref "R24") (pin "2") (pinfunction "2_2") (pintype "passive"))
    )
    (net (code "54") (name "Net-(C5-Pad2)") (class "Default")
      (node (ref "C5") (pin "2") (pinfunction "2_2") (pintype "passive"))
      (node (ref "R30") (pin "1") (pinfunction "1_1") (pintype "passive"))
      (node (ref "T3") (pin "B") (pinfunction "B_B") (pintype "passive"))
    )
    (net (code "55") (name "Net-(C9-Pad1)") (class "Default")
      (node (ref "C9") (pin "1") (pinfunction "1_1") (pintype "passive"))
      (node (ref "R35") (pin "2") (pinfunction "2_2") (pintype "passive"))
    )
    (net (code "56") (name "Net-(C10-Pad2)") (class "Default")
      (node (ref "C10") (pin "2") (pinfunction "2_2") (pintype "passive"))
      (node (ref "R36") (pin "1") (pinfunction "1_1") (pintype "passive"))
    )
    (net (code "57") (name "Net-(C17-Pad2)") (class "Default")
      (node (ref "C17") (pin "2") (pinfunction "2_2") (pintype "passive"))
      (node (ref "C18") (pin "1") (pinfunction "1_1") (pintype "passive"))
      (node (ref "R43") (pin "2") (pinfunction "2_2") (pintype "passive"))
    )
    (net (code "58") (name "Net-(C18-Pad2)") (class "Default")
      (node (ref "C18") (pin "2") (pinfunction "2_2") (pintype "passive"))
      (node (ref "Q2") (pin "2") (pinfunction "2_2") (pintype "passive"))
      (node (ref "R44") (pin "1") (pinfunction "1_1") (pintype "passive"))
    )
    (net (code "59") (name "Net-(C20-Pad1)") (class "Default")
      (node (ref "C20") (pin "1") (pinfunction "1_1") (pintype "passive"))
      (node (ref "Q2") (pin "1") (pinfunction "1_1") (pintype "passive"))
      (node (ref "R45") (pin "1") (pinfunction "1_1") (pintype "passive"))
    )
    (net (code "60") (name "Net-(C25-Pad+)") (class "Default")
      (node (ref "C25") (pin "+") (pinfunction "+_+") (pintype "passive"))
      (node (ref "C26") (pin "1") (pinfunction "1_1") (pintype "passive"))
      (node (ref "C27") (pin "1") (pinfunction "1_1") (pintype "passive"))
      (node (ref "R51") (pin "2") (pinfunction "2_2") (pintype "passive"))
      (node (ref "R52") (pin "1") (pinfunction "1_1") (pintype "passive"))
      (node (ref "R53") (pin "1") (pinfunction "1_1") (pintype "passive"))
      (node (ref "R58") (pin "1") (pinfunction "1_1") (pintype "passive"))
      (node (ref "T5") (pin "C") (pinfunction "C_C") (pintype "passive"))
    )
    (net (code "61") (name "Net-(C29-Pad-)") (class "Default")
      (node (ref "C29") (pin "-") (pinfunction "-_-") (pintype "passive"))
      (node (ref "R53") (pin "2") (pinfunction "2_2") (pintype "passive"))
      (node (ref "T5") (pin "B") (pinfunction "B_B") (pintype "passive"))
      (node (ref "T6") (pin "C") (pinfunction "C_C") (pintype "passive"))
    )
    (net (code "62") (name "Net-(D1-PadA)") (class "Default")
      (node (ref "D1") (pin "A") (pinfunction "A_A") (pintype "passive"))
      (node (ref "K1") (pin "4") (pinfunction "4_4") (pintype "passive"))
      (node (ref "K2") (pin "4") (pinfunction "4_4") (pintype "passive"))
      (node (ref "K3") (pin "4") (pinfunction "4_4") (pintype "passive"))
      (node (ref "K4") (pin "4") (pinfunction "4_4") (pintype "passive"))
      (node (ref "K5") (pin "4") (pinfunction "4_4") (pintype "passive"))
    )
    (net (code "63") (name "Net-(D2-PadA)") (class "Default")
      (node (ref "D2") (pin "A") (pinfunction "A_A") (pintype "passive"))
      (node (ref "KE") (pin "4") (pinfunction "4_4") (pintype "passive"))
      (node (ref "KQ") (pin "4") (pinfunction "4_4") (pintype "passive"))
      (node (ref "KR") (pin "4") (pinfunction "4_4") (pintype "passive"))
      (node (ref "KT") (pin "4") (pinfunction "4_4") (pintype "passive"))
      (node (ref "KW") (pin "4") (pinfunction "4_4") (pintype "passive"))
    )
    (net (code "64") (name "Net-(D3-PadA)") (class "Default")
      (node (ref "D3") (pin "A") (pinfunction "A_A") (pintype "passive"))
      (node (ref "KA") (pin "4") (pinfunction "4_4") (pintype "passive"))
      (node (ref "KD") (pin "4") (pinfunction "4_4") (pintype "passive"))
      (node (ref "KF") (pin "4") (pinfunction "4_4") (pintype "passive"))
      (node (ref "KG") (pin "4") (pinfunction "4_4") (pintype "passive"))
      (node (ref "KS") (pin "4") (pinfunction "4_4") (pintype "passive"))
    )
    (net (code "65") (name "Net-(D4-PadA)") (class "Default")
      (node (ref "D4") (pin "A") (pinfunction "A_A") (pintype "passive"))
      (node (ref "KC") (pin "4") (pinfunction "4_4") (pintype "passive"))
      (node (ref "KCAPS") (pin "4") (pinfunction "4_4") (pintype "passive"))
      (node (ref "KV") (pin "4") (pinfunction "4_4") (pintype "passive"))
      (node (ref "KX") (pin "4") (pinfunction "4_4") (pintype "passive"))
      (node (ref "KZ") (pin "4") (pinfunction "4_4") (pintype "passive"))
    )
    (net (code "66") (name "Net-(D5-PadA)") (class "Default")
      (node (ref "D5") (pin "A") (pinfunction "A_A") (pintype "passive"))
      (node (ref "K0") (pin "4") (pinfunction "4_4") (pintype "passive"))
      (node (ref "K6") (pin "4") (pinfunction "4_4") (pintype "passive"))
      (node (ref "K7") (pin "4") (pinfunction "4_4") (pintype "passive"))
      (node (ref "K8") (pin "4") (pinfunction "4_4") (pintype "passive"))
      (node (ref "K9") (pin "4") (pinfunction "4_4") (pintype "passive"))
    )
    (net (code "67") (name "Net-(D6-PadA)") (class "Default")
      (node (ref "D6") (pin "A") (pinfunction "A_A") (pintype "passive"))
      (node (ref "KI") (pin "4") (pinfunction "4_4") (pintype "passive"))
      (node (ref "KO") (pin "4") (pinfunction "4_4") (pintype "passive"))
      (node (ref "KP") (pin "4") (pinfunction "4_4") (pintype "passive"))
      (node (ref "KU") (pin "4") (pinfunction "4_4") (pintype "passive"))
      (node (ref "KY") (pin "4") (pinfunction "4_4") (pintype "passive"))
    )
    (net (code "68") (name "Net-(D7-PadA)") (class "Default")
      (node (ref "D7") (pin "A") (pinfunction "A_A") (pintype "passive"))
      (node (ref "KENT") (pin "4") (pinfunction "4_4") (pintype "passive"))
      (node (ref "KH") (pin "4") (pinfunction "4_4") (pintype "passive"))
      (node (ref "KJ") (pin "4") (pinfunction "4_4") (pintype "passive"))
      (node (ref "KK") (pin "4") (pinfunction "4_4") (pintype "passive"))
      (node (ref "KL") (pin "4") (pinfunction "4_4") (pintype "passive"))
    )
    (net (code "69") (name "Net-(D8-PadA)") (class "Default")
      (node (ref "D8") (pin "A") (pinfunction "A_A") (pintype "passive"))
      (node (ref "KB") (pin "4") (pinfunction "4_4") (pintype "passive"))
      (node (ref "KM") (pin "4") (pinfunction "4_4") (pintype "passive"))
      (node (ref "KN") (pin "4") (pinfunction "4_4") (pintype "passive"))
      (node (ref "KSPACE") (pin "4") (pinfunction "4_4") (pintype "passive"))
      (node (ref "KSYM") (pin "4") (pinfunction "4_4") (pintype "passive"))
    )
    (net (code "70") (name "Net-(D10-PadC)") (class "Default")
      (node (ref "D10") (pin "C") (pinfunction "C_C") (pintype "passive"))
      (node (ref "T2") (pin "B") (pinfunction "B_B") (pintype "passive"))
    )
    (net (code "71") (name "Net-(Q1-2)") (class "Default")
      (node (ref "Q1") (pin "3") (pinfunction "2_3") (pintype "passive"))
      (node (ref "ULA") (pin "39") (pinfunction "OSC_39") (pintype "output"))
    )
    (net (code "72") (name "Net-(R54-Pad1)") (class "Default")
      (node (ref "R54") (pin "1") (pinfunction "1_1") (pintype "passive"))
      (node (ref "T6") (pin "E") (pinfunction "E_E") (pintype "passive"))
    )
    (net (code "73") (name "Net-(R56-Pad1)") (class "Default")
      (node (ref "R56") (pin "1") (pinfunction "1_1") (pintype "passive"))
      (node (ref "R57") (pin "2") (pinfunction "2_2") (pintype "passive"))
      (node (ref "R58") (pin "2") (pinfunction "2_2") (pintype "passive"))
      (node (ref "T6") (pin "B") (pinfunction "B_B") (pintype "passive"))
    )
    (net (code "74") (name "Net-(SPKR-Pad1)") (class "Default")
      (node (ref "SPKR") (pin "1") (pinfunction "1_1") (pintype "passive"))
      (node (ref "T2") (pin "E") (pinfunction "E_E") (pintype "passive"))
    )
    (net (code "75") (name "Net-(T1-B)") (class "Default")
      (node (ref "C13") (pin "2") (pinfunction "2_2") (pintype "passive"))
      (node (ref "R39") (pin "1") (pinfunction "1_1") (pintype "passive"))
      (node (ref "T1") (pin "1") (pinfunction "B_1") (pintype "passive"))
    )
    (net (code "76") (name "Net-(T1-C)") (class "Default")
      (node (ref "C16") (pin "1") (pinfunction "1_1") (pintype "passive"))
      (node (ref "R47") (pin "1") (pinfunction "1_1") (pintype "passive"))
      (node (ref "T1") (pin "3") (pinfunction "C_3") (pintype "passive"))
    )
    (net (code "77") (name "Net-(T4-B)") (class "Default")
      (node (ref "C12") (pin "2") (pinfunction "2_2") (pintype "passive"))
      (node (ref "R38") (pin "1") (pinfunction "1_1") (pintype "passive"))
      (node (ref "T4") (pin "1") (pinfunction "B_1") (pintype "passive"))
    )
    (net (code "78") (name "Net-(T4-C)") (class "Default")
      (node (ref "C15") (pin "1") (pinfunction "1_1") (pintype "passive"))
      (node (ref "R48") (pin "1") (pinfunction "1_1") (pintype "passive"))
      (node (ref "T4") (pin "3") (pinfunction "C_3") (pintype "passive"))
    )
    (net (code "79") (name "Net-(U$1-Q0)") (class "Default")
      (node (ref "U$1") (pin "19") (pinfunction "Q0_19") (pintype "bidirectional"))
      (node (ref "ULA_RAM") (pin "5") (pinfunction "A9_5") (pintype "input"))
    )
    (net (code "80") (name "Net-(U$1-Q1)") (class "Default")
      (node (ref "U$1") (pin "18") (pinfunction "Q1_18") (pintype "bidirectional"))
      (node (ref "ULA_RAM") (pin "3") (pinfunction "A7_3") (pintype "input"))
    )
    (net (code "81") (name "Net-(U$1-Q2)") (class "Default")
      (node (ref "U$1") (pin "17") (pinfunction "Q2_17") (pintype "bidirectional"))
      (node (ref "ULA_RAM") (pin "2") (pinfunction "A6_2") (pintype "input"))
    )
    (net (code "82") (name "Net-(U$1-Q3)") (class "Default")
      (node (ref "U$1") (pin "16") (pinfunction "Q3_16") (pintype "bidirectional"))
      (node (ref "ULA_RAM") (pin "26") (pinfunction "A4_26") (pintype "input"))
    )
    (net (code "83") (name "Net-(U$1-Q4)") (class "Default")
      (node (ref "U$1") (pin "15") (pinfunction "Q4_15") (pintype "bidirectional"))
      (node (ref "ULA_RAM") (pin "24") (pinfunction "A2_24") (pintype "input"))
    )
    (net (code "84") (name "Net-(U$1-Q5)") (class "Default")
      (node (ref "U$1") (pin "14") (pinfunction "Q5_14") (pintype "bidirectional"))
      (node (ref "ULA_RAM") (pin "23") (pinfunction "A1_23") (pintype "input"))
    )
    (net (code "85") (name "Net-(U$1-Q6)") (class "Default")
      (node (ref "U$1") (pin "13") (pinfunction "Q6_13") (pintype "bidirectional"))
      (node (ref "ULA_RAM") (pin "21") (pinfunction "A0_21") (pintype "input"))
    )
    (net (code "86") (name "Net-(U$2-CHROMA_BIAS)") (class "Default")
      (node (ref "C14") (pin "1") (pinfunction "1_1") (pintype "passive"))
      (node (ref "R40") (pin "2") (pinfunction "2_2") (pintype "passive"))
      (node (ref "U$2") (pin "3") (pinfunction "CHROMA_BIAS_3") (pintype "bidirectional"))
    )
    (net (code "87") (name "Net-(U$2-CHROMA_LAG)") (class "Default")
      (node (ref "C19") (pin "1") (pinfunction "1_1") (pintype "passive"))
      (node (ref "R44") (pin "2") (pinfunction "2_2") (pintype "passive"))
      (node (ref "U$2") (pin "18") (pinfunction "CHROMA_LAG_18") (pintype "bidirectional"))
    )
    (net (code "88") (name "Net-(U$2-CHROMA_LEAD)") (class "Default")
      (node (ref "C17") (pin "1") (pinfunction "1_1") (pintype "passive"))
      (node (ref "U$2") (pin "1") (pinfunction "CHROMA_LEAD_1") (pintype "bidirectional"))
    )
    (net (code "89") (name "Net-(U$2-CHROMA_OSC)") (class "Default")
      (node (ref "R45") (pin "2") (pinfunction "2_2") (pintype "passive"))
      (node (ref "R46") (pin "1") (pinfunction "1_1") (pintype "passive"))
      (node (ref "U$2") (pin "17") (pinfunction "CHROMA_OSC_17") (pintype "bidirectional"))
    )
    (net (code "90") (name "Net-(U$2-CHROMA_SUB)") (class "Default")
      (node (ref "C29") (pin "+") (pinfunction "+_+") (pintype "passive"))
      (node (ref "R51") (pin "1") (pinfunction "1_1") (pintype "passive"))
      (node (ref "U$2") (pin "13") (pinfunction "CHROMA_SUB_13") (pintype "bidirectional"))
    )
    (net (code "91") (name "Net-(U$2-U_INPUT)") (class "Default")
      (node (ref "C22") (pin "1") (pinfunction "1_1") (pintype "passive"))
      (node (ref "R47") (pin "2") (pinfunction "2_2") (pintype "passive"))
      (node (ref "U$2") (pin "4") (pinfunction "U_INPUT_4") (pintype "bidirectional"))
    )
    (net (code "92") (name "Net-(U$2-VIDEO_INPUT)") (class "Default")
      (node (ref "R49") (pin "2") (pinfunction "2_2") (pintype "passive"))
      (node (ref "U$2") (pin "12") (pinfunction "VIDEO_INPUT_12") (pintype "bidirectional"))
    )
    (net (code "93") (name "Net-(U$2-V_INPUT)") (class "Default")
      (node (ref "C21") (pin "1") (pinfunction "1_1") (pintype "passive"))
      (node (ref "R48") (pin "2") (pinfunction "2_2") (pintype "passive"))
      (node (ref "U$2") (pin "2") (pinfunction "V_INPUT_2") (pintype "bidirectional"))
    )
    (net (code "94") (name "Net-(U$3-S)") (class "Default")
      (node (ref "REGS") (pin "3") (pinfunction "3_3") (pintype "passive"))
      (node (ref "REGS") (pin "4") (pinfunction "4_4") (pintype "passive"))
      (node (ref "U$3") (pin "3") (pinfunction "S_3") (pintype "passive"))
      (node (ref "VPOW") (pin "2") (pinfunction "2_2") (pintype "passive"))
    )
    (net (code "95") (name "Net-(ULA-CASL)") (class "Default")
      (node (ref "ULA") (pin "1") (pinfunction "CASL_1") (pintype "output"))
      (node (ref "ULA_RAM") (pin "20") (pinfunction "~{CE}_20") (pintype "input"))
    )
    (net (code "96") (name "Net-(ULA-CASS{slash}SPKR)") (class "Default")
      (node (ref "C10") (pin "1") (pinfunction "1_1") (pintype "passive"))
      (node (ref "C11") (pin "1") (pinfunction "1_1") (pintype "passive"))
      (node (ref "D10") (pin "A") (pinfunction "A_A") (pintype "passive"))
      (node (ref "D9") (pin "C") (pinfunction "C_C") (pintype "passive"))
      (node (ref "R34") (pin "2") (pinfunction "2_2") (pintype "passive"))
      (node (ref "R35") (pin "1") (pinfunction "1_1") (pintype "passive"))
      (node (ref "ULA") (pin "28") (pinfunction "CASS/SPKR_28") (pintype "output"))
    )
    (net (code "97") (name "Net-(ULA-D0)") (class "Default")
      (node (ref "R4") (pin "2") (pinfunction "2_2") (pintype "passive"))
      (node (ref "ULA") (pin "18") (pinfunction "D0_18") (pintype "bidirectional"))
      (node (ref "ULA_RAM") (pin "11") (pinfunction "DQ0_11") (pintype "bidirectional"))
    )
    (net (code "98") (name "Net-(ULA-D1)") (class "Default")
      (node (ref "R5") (pin "2") (pinfunction "2_2") (pintype "passive"))
      (node (ref "ULA") (pin "21") (pinfunction "D1_21") (pintype "bidirectional"))
      (node (ref "ULA_RAM") (pin "12") (pinfunction "DQ1_12") (pintype "bidirectional"))
    )
    (net (code "99") (name "Net-(ULA-D2)") (class "Default")
      (node (ref "R6") (pin "2") (pinfunction "2_2") (pintype "passive"))
      (node (ref "ULA") (pin "22") (pinfunction "D2_22") (pintype "bidirectional"))
      (node (ref "ULA_RAM") (pin "13") (pinfunction "DQ2_13") (pintype "bidirectional"))
    )
    (net (code "100") (name "Net-(ULA-D3)") (class "Default")
      (node (ref "R1") (pin "2") (pinfunction "2_2") (pintype "passive"))
      (node (ref "ULA") (pin "25") (pinfunction "D3_25") (pintype "bidirectional"))
      (node (ref "ULA_RAM") (pin "15") (pinfunction "DQ3_15") (pintype "bidirectional"))
    )
    (net (code "101") (name "Net-(ULA-D4)") (class "Default")
      (node (ref "R2") (pin "2") (pinfunction "2_2") (pintype "passive"))
      (node (ref "ULA") (pin "27") (pinfunction "D4_27") (pintype "bidirectional"))
      (node (ref "ULA_RAM") (pin "16") (pinfunction "DQ4_16") (pintype "bidirectional"))
    )
    (net (code "102") (name "Net-(ULA-D5)") (class "Default")
      (node (ref "R3") (pin "2") (pinfunction "2_2") (pintype "passive"))
      (node (ref "ULA") (pin "29") (pinfunction "D5_29") (pintype "bidirectional"))
      (node (ref "ULA_RAM") (pin "17") (pinfunction "DQ5_17") (pintype "bidirectional"))
    )
    (net (code "103") (name "Net-(ULA-D6)") (class "Default")
      (node (ref "R7") (pin "2") (pinfunction "2_2") (pintype "passive"))
      (node (ref "ULA") (pin "30") (pinfunction "D6_30") (pintype "bidirectional"))
      (node (ref "ULA_RAM") (pin "18") (pinfunction "DQ6_18") (pintype "bidirectional"))
    )
    (net (code "104") (name "Net-(ULA-D7)") (class "Default")
      (node (ref "R8") (pin "2") (pinfunction "2_2") (pintype "passive"))
      (node (ref "ULA") (pin "31") (pinfunction "D7_31") (pintype "bidirectional"))
      (node (ref "ULA_RAM") (pin "19") (pinfunction "DQ7_19") (pintype "bidirectional"))
    )
    (net (code "105") (name "Net-(ULA-DRAMWEL)") (class "Default")
      (node (ref "ULA") (pin "4") (pinfunction "DRAMWEL_4") (pintype "output"))
      (node (ref "ULA_RAM") (pin "27") (pinfunction "~{WE}_27") (pintype "input"))
    )
    (net (code "106") (name "Net-(ULA-VCC{slash}VAN)") (class "Default")
      (node (ref "C7") (pin "1") (pinfunction "1_1") (pintype "passive"))
      (node (ref "R33") (pin "1") (pinfunction "1_1") (pintype "passive"))
      (node (ref "ULA") (pin "13") (pinfunction "VCC/VAN_13") (pintype "output"))
    )
    (net (code "107") (name "Net-(Z80A-BUSRQ)") (class "Default")
      (node (ref "R62") (pin "2") (pinfunction "2_2") (pintype "passive"))
      (node (ref "Z80A") (pin "25") (pinfunction "BUSRQ_25") (pintype "input"))
    )
    (net (code "108") (name "Net-(Z80A-NMI)") (class "Default")
      (node (ref "R61") (pin "2") (pinfunction "2_2") (pintype "passive"))
      (node (ref "Z80A") (pin "17") (pinfunction "NMI_17") (pintype "input"))
    )
    (net (code "109") (name "Net-(Z80A-RESET)") (class "Default")
      (node (ref "K10") (pin "3") (pinfunction "3_3") (pintype "passive"))
      (node (ref "R59") (pin "1") (pinfunction "1_1") (pintype "passive"))
      (node (ref "Z80A") (pin "26") (pinfunction "RESET_26") (pintype "input"))
    )
    (net (code "110") (name "Net-(Z80A-WAIT)") (class "Default")
      (node (ref "R60") (pin "2") (pinfunction "2_2") (pintype "passive"))
      (node (ref "Z80A") (pin "24") (pinfunction "WAIT_24") (pintype "input"))
    )
    (net (code "111") (name "PHICPU") (class "Default")
      (node (ref "C5") (pin "1") (pinfunction "1_1") (pintype "passive"))
      (node (ref "R30") (pin "2") (pinfunction "2_2") (pintype "passive"))
      (node (ref "R32") (pin "2") (pinfunction "2_2") (pintype "passive"))
      (node (ref "ULA") (pin "32") (pinfunction "PHICPU_32") (pintype "output"))
    )
    (net (code "112") (name "RAM_CE") (class "Default")
      (node (ref "32KRAM") (pin "20") (pinfunction "~{CE}_20") (pintype "input"))
      (node (ref "IC3") (pin "2") (pinfunction "O_2") (pintype "output"))
    )
    (net (code "113") (name "RAM_OE") (class "Default")
      (node (ref "32KRAM") (pin "22") (pinfunction "~{OE}_22") (pintype "input"))
      (node (ref "IC1") (pin "3") (pinfunction "O_3") (pintype "output"))
    )
    (net (code "114") (name "RAM_WE") (class "Default")
      (node (ref "32KRAM") (pin "27") (pinfunction "~{WE}_27") (pintype "input"))
      (node (ref "IC1") (pin "6") (pinfunction "O_6") (pintype "output"))
    )
    (net (code "115") (name "RASL") (class "Default")
      (node (ref "IC3") (pin "13") (pinfunction "I_13") (pintype "input"))
      (node (ref "R25") (pin "2") (pinfunction "2_2") (pintype "passive"))
      (node (ref "ULA") (pin "35") (pinfunction "RASL_35") (pintype "output"))
    )
    (net (code "116") (name "READ") (class "Default")
      (node (ref "IC1") (pin "1") (pinfunction "I0_1") (pintype "input"))
      (node (ref "ULA") (pin "3") (pinfunction "RDL_3") (pintype "output"))
      (node (ref "Z80A") (pin "21") (pinfunction "RD_21") (pintype "output"))
    )
    (net (code "117") (name "ROM_CE") (class "Default")
      (node (ref "32K_ROM") (pin "23") (pinfunction "~{CE}_23") (pintype "input"))
    )
    (net (code "118") (name "ROM_CS") (class "Default")
      (node (ref "R63") (pin "1") (pinfunction "1_1") (pintype "passive"))
      (node (ref "ULA") (pin "34") (pinfunction "ROMCSL_34") (pintype "output"))
    )
    (net (code "119") (name "URAMA0") (class "Default")
      (node (ref "R20") (pin "2") (pinfunction "2_2") (pintype "passive"))
      (node (ref "U$1") (pin "6") (pinfunction "D4_6") (pintype "bidirectional"))
      (node (ref "ULA") (pin "5") (pinfunction "DMA0_5") (pintype "output"))
      (node (ref "ULA_RAM") (pin "8") (pinfunction "A12_8") (pintype "input"))
    )
    (net (code "120") (name "URAMA1") (class "Default")
      (node (ref "R19") (pin "2") (pinfunction "2_2") (pintype "passive"))
      (node (ref "U$1") (pin "3") (pinfunction "D1_3") (pintype "bidirectional"))
      (node (ref "ULA") (pin "6") (pinfunction "DMA1_6") (pintype "output"))
      (node (ref "ULA_RAM") (pin "4") (pinfunction "A8_4") (pintype "input"))
    )
    (net (code "121") (name "URAMA2") (class "Default")
      (node (ref "R18") (pin "2") (pinfunction "2_2") (pintype "passive"))
      (node (ref "U$1") (pin "8") (pinfunction "D6_8") (pintype "bidirectional"))
      (node (ref "ULA") (pin "7") (pinfunction "DMA2_7") (pintype "output"))
      (node (ref "ULA_RAM") (pin "25") (pinfunction "A3_25") (pintype "input"))
    )
    (net (code "122") (name "URAMA3") (class "Default")
      (node (ref "R17") (pin "2") (pinfunction "2_2") (pintype "passive"))
      (node (ref "U$1") (pin "5") (pinfunction "D3_5") (pintype "bidirectional"))
      (node (ref "ULA") (pin "8") (pinfunction "DMA3_8") (pintype "input"))
      (node (ref "ULA_RAM") (pin "6") (pinfunction "A10_6") (pintype "input"))
    )
    (net (code "123") (name "URAMA4") (class "Default")
      (node (ref "R24") (pin "1") (pinfunction "1_1") (pintype "passive"))
      (node (ref "U$1") (pin "4") (pinfunction "D2_4") (pintype "bidirectional"))
      (node (ref "ULA") (pin "9") (pinfunction "DMA4_9") (pintype "input"))
      (node (ref "ULA_RAM") (pin "7") (pinfunction "A11_7") (pintype "input"))
    )
    (net (code "124") (name "URAMA5") (class "Default")
      (node (ref "R23") (pin "1") (pinfunction "1_1") (pintype "passive"))
      (node (ref "U$1") (pin "2") (pinfunction "D0_2") (pintype "bidirectional"))
      (node (ref "ULA") (pin "10") (pinfunction "DMA5_10") (pintype "input"))
      (node (ref "ULA_RAM") (pin "9") (pinfunction "A13_9") (pintype "input"))
    )
    (net (code "125") (name "URAMA6") (class "Default")
      (node (ref "R22") (pin "1") (pinfunction "1_1") (pintype "passive"))
      (node (ref "U$1") (pin "7") (pinfunction "D5_7") (pintype "bidirectional"))
      (node (ref "ULA") (pin "11") (pinfunction "DMA6_11") (pintype "input"))
      (node (ref "ULA_RAM") (pin "1") (pinfunction "A5_1") (pintype "input"))
    )
    (net (code "126") (name "VCC") (class "Default")
      (node (ref "157") (pin "16") (pinfunction "VCC_16") (pintype "bidirectional"))
      (node (ref "157-1") (pin "16") (pinfunction "VCC_16") (pintype "bidirectional"))
      (node (ref "32KRAM") (pin "28") (pinfunction "VCC_28") (pintype "power_in"))
      (node (ref "32K_ROM") (pin "2") (pinfunction "VPP_2") (pintype "input"))
      (node (ref "32K_ROM") (pin "32") (pinfunction "VCC_32") (pintype "power_in"))
      (node (ref "C1") (pin "1") (pinfunction "1_1") (pintype "passive"))
      (node (ref "C2") (pin "1") (pinfunction "1_1") (pintype "passive"))
      (node (ref "C3") (pin "1") (pinfunction "1_1") (pintype "passive"))
      (node (ref "C30") (pin "+") (pinfunction "+_+") (pintype "passive"))
      (node (ref "C4") (pin "1") (pinfunction "1_1") (pintype "passive"))
      (node (ref "C6") (pin "1") (pinfunction "1_1") (pintype "passive"))
      (node (ref "C8") (pin "1") (pinfunction "1_1") (pintype "passive"))
      (node (ref "IC1") (pin "14") (pinfunction "VCC_14") (pintype "power_in"))
      (node (ref "IC3") (pin "14") (pinfunction "VCC_14") (pintype "power_in"))
      (node (ref "R10") (pin "2") (pinfunction "2_2") (pintype "passive"))
      (node (ref "R11") (pin "2") (pinfunction "2_2") (pintype "passive"))
      (node (ref "R12") (pin "2") (pinfunction "2_2") (pintype "passive"))
      (node (ref "R13") (pin "2") (pinfunction "2_2") (pintype "passive"))
      (node (ref "R14") (pin "2") (pinfunction "2_2") (pintype "passive"))
      (node (ref "R15") (pin "2") (pinfunction "2_2") (pintype "passive"))
      (node (ref "R16") (pin "2") (pinfunction "2_2") (pintype "passive"))
      (node (ref "R21") (pin "2") (pinfunction "2_2") (pintype "passive"))
      (node (ref "R26") (pin "2") (pinfunction "2_2") (pintype "passive"))
      (node (ref "R27") (pin "2") (pinfunction "2_2") (pintype "passive"))
      (node (ref "R28") (pin "2") (pinfunction "2_2") (pintype "passive"))
      (node (ref "R29") (pin "2") (pinfunction "2_2") (pintype "passive"))
      (node (ref "R31") (pin "1") (pinfunction "1_1") (pintype "passive"))
      (node (ref "R32") (pin "1") (pinfunction "1_1") (pintype "passive"))
      (node (ref "R33") (pin "2") (pinfunction "2_2") (pintype "passive"))
      (node (ref "R34") (pin "1") (pinfunction "1_1") (pintype "passive"))
      (node (ref "R38") (pin "2") (pinfunction "2_2") (pintype "passive"))
      (node (ref "R39") (pin "2") (pinfunction "2_2") (pintype "passive"))
      (node (ref "R40") (pin "1") (pinfunction "1_1") (pintype "passive"))
      (node (ref "R52") (pin "2") (pinfunction "2_2") (pintype "passive"))
      (node (ref "R59") (pin "2") (pinfunction "2_2") (pintype "passive"))
      (node (ref "R60") (pin "1") (pinfunction "1_1") (pintype "passive"))
      (node (ref "R61") (pin "1") (pinfunction "1_1") (pintype "passive"))
      (node (ref "R62") (pin "1") (pinfunction "1_1") (pintype "passive"))
      (node (ref "R9") (pin "2") (pinfunction "2_2") (pintype "passive"))
      (node (ref "REGS") (pin "1") (pinfunction "1_1") (pintype "passive"))
      (node (ref "ROMS") (pin "3") (pinfunction "3_3") (pintype "passive"))
      (node (ref "T1") (pin "2") (pinfunction "E_2") (pintype "passive"))
      (node (ref "T2") (pin "C") (pinfunction "C_C") (pintype "passive"))
      (node (ref "T4") (pin "2") (pinfunction "E_2") (pintype "passive"))
      (node (ref "T7") (pin "C") (pinfunction "C_C") (pintype "passive"))
      (node (ref "U$1") (pin "20") (pinfunction "VCC_20") (pintype "bidirectional"))
      (node (ref "ULA") (pin "14") (pinfunction "VCC_14") (pintype "output"))
      (node (ref "ULA_RAM") (pin "28") (pinfunction "VCC_28") (pintype "power_in"))
      (node (ref "Z80A") (pin "11") (pinfunction "VCC_11") (pintype "power_in"))
    )
    (net (code "127") (name "VIDEO") (class "Default")
      (node (ref "R55") (pin "1") (pinfunction "1_1") (pintype "passive"))
      (node (ref "T5") (pin "E") (pinfunction "E_E") (pintype "passive"))
      (node (ref "VID") (pin "1") (pinfunction "1_1") (pintype "passive"))
    )
    (net (code "128") (name "VID_U") (class "Default")
      (node (ref "C16") (pin "2") (pinfunction "2_2") (pintype "passive"))
      (node (ref "R42") (pin "1") (pinfunction "1_1") (pintype "passive"))
      (node (ref "ULA") (pin "15") (pinfunction "U_15") (pintype "output"))
    )
    (net (code "129") (name "VID_V") (class "Default")
      (node (ref "C15") (pin "2") (pinfunction "2_2") (pintype "passive"))
      (node (ref "R41") (pin "1") (pinfunction "1_1") (pintype "passive"))
      (node (ref "ULA") (pin "16") (pinfunction "V_16") (pintype "output"))
    )
    (net (code "130") (name "VID_YL") (class "Default")
      (node (ref "C12") (pin "1") (pinfunction "1_1") (pintype "passive"))
      (node (ref "C13") (pin "1") (pinfunction "1_1") (pintype "passive"))
      (node (ref "R50") (pin "2") (pinfunction "2_2") (pintype "passive"))
      (node (ref "R57") (pin "1") (pinfunction "1_1") (pintype "passive"))
      (node (ref "ULA") (pin "17") (pinfunction "YL_17") (pintype "output"))
    )
    (net (code "131") (name "WRITE") (class "Default")
      (node (ref "IC1") (pin "5") (pinfunction "I1_5") (pintype "input"))
      (node (ref "ULA") (pin "2") (pinfunction "WRL_2") (pintype "output"))
      (node (ref "Z80A") (pin "22") (pinfunction "WR_22") (pintype "output"))
    )
    (net (code "132") (name "unconnected-(157-1-3A-Pad11)") (class "Default")
      (node (ref "157-1") (pin "11") (pinfunction "3A_11") (pintype "bidirectional"))
    )
    (net (code "133") (name "unconnected-(157-1-3B-Pad10)") (class "Default")
      (node (ref "157-1") (pin "10") (pinfunction "3B_10") (pintype "bidirectional"))
    )
    (net (code "134") (name "unconnected-(157-1-3Y-Pad9)") (class "Default")
      (node (ref "157-1") (pin "9") (pinfunction "3Y_9") (pintype "bidirectional"))
    )
    (net (code "135") (name "unconnected-(IC1C-I0-Pad9)") (class "Default")
      (node (ref "IC1") (pin "9") (pinfunction "I0_9") (pintype "input"))
    )
    (net (code "136") (name "unconnected-(IC1C-I1-Pad10)") (class "Default")
      (node (ref "IC1") (pin "10") (pinfunction "I1_10") (pintype "input"))
    )
    (net (code "137") (name "unconnected-(IC1C-O-Pad8)") (class "Default")
      (node (ref "IC1") (pin "8") (pinfunction "O_8") (pintype "output"))
    )
    (net (code "138") (name "unconnected-(IC1D-I0-Pad12)") (class "Default")
      (node (ref "IC1") (pin "12") (pinfunction "I0_12") (pintype "input"))
    )
    (net (code "139") (name "unconnected-(IC1D-I1-Pad13)") (class "Default")
      (node (ref "IC1") (pin "13") (pinfunction "I1_13") (pintype "input"))
    )
    (net (code "140") (name "unconnected-(IC1D-O-Pad11)") (class "Default")
      (node (ref "IC1") (pin "11") (pinfunction "O_11") (pintype "output"))
    )
    (net (code "141") (name "unconnected-(IC3B-I-Pad3)") (class "Default")
      (node (ref "IC3") (pin "3") (pinfunction "I_3") (pintype "input"))
    )
    (net (code "142") (name "unconnected-(IC3B-O-Pad4)") (class "Default")
      (node (ref "IC3") (pin "4") (pinfunction "O_4") (pintype "output"))
    )
    (net (code "143") (name "unconnected-(IC3C-I-Pad5)") (class "Default")
      (node (ref "IC3") (pin "5") (pinfunction "I_5") (pintype "input"))
    )
    (net (code "144") (name "unconnected-(IC3C-O-Pad6)") (class "Default")
      (node (ref "IC3") (pin "6") (pinfunction "O_6") (pintype "output"))
    )
    (net (code "145") (name "unconnected-(IC3D-I-Pad9)") (class "Default")
      (node (ref "IC3") (pin "9") (pinfunction "I_9") (pintype "input"))
    )
    (net (code "146") (name "unconnected-(IC3D-O-Pad8)") (class "Default")
      (node (ref "IC3") (pin "8") (pinfunction "O_8") (pintype "output"))
    )
    (net (code "147") (name "unconnected-(IC3E-I-Pad11)") (class "Default")
      (node (ref "IC3") (pin "11") (pinfunction "I_11") (pintype "input"))
    )
    (net (code "148") (name "unconnected-(IC3E-O-Pad10)") (class "Default")
      (node (ref "IC3") (pin "10") (pinfunction "O_10") (pintype "output"))
    )
    (net (code "149") (name "unconnected-(K0-Pad2)") (class "Default")
      (node (ref "K0") (pin "2") (pinfunction "2_2") (pintype "passive"))
    )
    (net (code "150") (name "unconnected-(K0-Pad3)") (class "Default")
      (node (ref "K0") (pin "3") (pinfunction "3_3") (pintype "passive"))
    )
    (net (code "151") (name "unconnected-(K1-Pad2)") (class "Default")
      (node (ref "K1") (pin "2") (pinfunction "2_2") (pintype "passive"))
    )
    (net (code "152") (name "unconnected-(K1-Pad3)") (class "Default")
      (node (ref "K1") (pin "3") (pinfunction "3_3") (pintype "passive"))
    )
    (net (code "153") (name "unconnected-(K2-Pad2)") (class "Default")
      (node (ref "K2") (pin "2") (pinfunction "2_2") (pintype "passive"))
    )
    (net (code "154") (name "unconnected-(K2-Pad3)") (class "Default")
      (node (ref "K2") (pin "3") (pinfunction "3_3") (pintype "passive"))
    )
    (net (code "155") (name "unconnected-(K3-Pad2)") (class "Default")
      (node (ref "K3") (pin "2") (pinfunction "2_2") (pintype "passive"))
    )
    (net (code "156") (name "unconnected-(K3-Pad3)") (class "Default")
      (node (ref "K3") (pin "3") (pinfunction "3_3") (pintype "passive"))
    )
    (net (code "157") (name "unconnected-(K4-Pad2)") (class "Default")
      (node (ref "K4") (pin "2") (pinfunction "2_2") (pintype "passive"))
    )
    (net (code "158") (name "unconnected-(K4-Pad3)") (class "Default")
      (node (ref "K4") (pin "3") (pinfunction "3_3") (pintype "passive"))
    )
    (net (code "159") (name "unconnected-(K5-Pad2)") (class "Default")
      (node (ref "K5") (pin "2") (pinfunction "2_2") (pintype "passive"))
    )
    (net (code "160") (name "unconnected-(K5-Pad3)") (class "Default")
      (node (ref "K5") (pin "3") (pinfunction "3_3") (pintype "passive"))
    )
    (net (code "161") (name "unconnected-(K6-Pad2)") (class "Default")
      (node (ref "K6") (pin "2") (pinfunction "2_2") (pintype "passive"))
    )
    (net (code "162") (name "unconnected-(K6-Pad3)") (class "Default")
      (node (ref "K6") (pin "3") (pinfunction "3_3") (pintype "passive"))
    )
    (net (code "163") (name "unconnected-(K7-Pad2)") (class "Default")
      (node (ref "K7") (pin "2") (pinfunction "2_2") (pintype "passive"))
    )
    (net (code "164") (name "unconnected-(K7-Pad3)") (class "Default")
      (node (ref "K7") (pin "3") (pinfunction "3_3") (pintype "passive"))
    )
    (net (code "165") (name "unconnected-(K8-Pad2)") (class "Default")
      (node (ref "K8") (pin "2") (pinfunction "2_2") (pintype "passive"))
    )
    (net (code "166") (name "unconnected-(K8-Pad3)") (class "Default")
      (node (ref "K8") (pin "3") (pinfunction "3_3") (pintype "passive"))
    )
    (net (code "167") (name "unconnected-(K9-Pad2)") (class "Default")
      (node (ref "K9") (pin "2") (pinfunction "2_2") (pintype "passive"))
    )
    (net (code "168") (name "unconnected-(K9-Pad3)") (class "Default")
      (node (ref "K9") (pin "3") (pinfunction "3_3") (pintype "passive"))
    )
    (net (code "169") (name "unconnected-(K10-Pad2)") (class "Default")
      (node (ref "K10") (pin "2") (pinfunction "2_2") (pintype "passive"))
    )
    (net (code "170") (name "unconnected-(K10-Pad4)") (class "Default")
      (node (ref "K10") (pin "4") (pinfunction "4_4") (pintype "passive"))
    )
    (net (code "171") (name "unconnected-(KA-Pad2)") (class "Default")
      (node (ref "KA") (pin "2") (pinfunction "2_2") (pintype "passive"))
    )
    (net (code "172") (name "unconnected-(KA-Pad3)") (class "Default")
      (node (ref "KA") (pin "3") (pinfunction "3_3") (pintype "passive"))
    )
    (net (code "173") (name "unconnected-(KB-Pad2)") (class "Default")
      (node (ref "KB") (pin "2") (pinfunction "2_2") (pintype "passive"))
    )
    (net (code "174") (name "unconnected-(KB-Pad3)") (class "Default")
      (node (ref "KB") (pin "3") (pinfunction "3_3") (pintype "passive"))
    )
    (net (code "175") (name "unconnected-(KC-Pad2)") (class "Default")
      (node (ref "KC") (pin "2") (pinfunction "2_2") (pintype "passive"))
    )
    (net (code "176") (name "unconnected-(KC-Pad3)") (class "Default")
      (node (ref "KC") (pin "3") (pinfunction "3_3") (pintype "passive"))
    )
    (net (code "177") (name "unconnected-(KCAPS-Pad2)") (class "Default")
      (node (ref "KCAPS") (pin "2") (pinfunction "2_2") (pintype "passive"))
    )
    (net (code "178") (name "unconnected-(KCAPS-Pad3)") (class "Default")
      (node (ref "KCAPS") (pin "3") (pinfunction "3_3") (pintype "passive"))
    )
    (net (code "179") (name "unconnected-(KD-Pad2)") (class "Default")
      (node (ref "KD") (pin "2") (pinfunction "2_2") (pintype "passive"))
    )
    (net (code "180") (name "unconnected-(KD-Pad3)") (class "Default")
      (node (ref "KD") (pin "3") (pinfunction "3_3") (pintype "passive"))
    )
    (net (code "181") (name "unconnected-(KE-Pad2)") (class "Default")
      (node (ref "KE") (pin "2") (pinfunction "2_2") (pintype "passive"))
    )
    (net (code "182") (name "unconnected-(KE-Pad3)") (class "Default")
      (node (ref "KE") (pin "3") (pinfunction "3_3") (pintype "passive"))
    )
    (net (code "183") (name "unconnected-(KENT-Pad2)") (class "Default")
      (node (ref "KENT") (pin "2") (pinfunction "2_2") (pintype "passive"))
    )
    (net (code "184") (name "unconnected-(KENT-Pad3)") (class "Default")
      (node (ref "KENT") (pin "3") (pinfunction "3_3") (pintype "passive"))
    )
    (net (code "185") (name "unconnected-(KF-Pad2)") (class "Default")
      (node (ref "KF") (pin "2") (pinfunction "2_2") (pintype "passive"))
    )
    (net (code "186") (name "unconnected-(KF-Pad3)") (class "Default")
      (node (ref "KF") (pin "3") (pinfunction "3_3") (pintype "passive"))
    )
    (net (code "187") (name "unconnected-(KG-Pad2)") (class "Default")
      (node (ref "KG") (pin "2") (pinfunction "2_2") (pintype "passive"))
    )
    (net (code "188") (name "unconnected-(KG-Pad3)") (class "Default")
      (node (ref "KG") (pin "3") (pinfunction "3_3") (pintype "passive"))
    )
    (net (code "189") (name "unconnected-(KH-Pad2)") (class "Default")
      (node (ref "KH") (pin "2") (pinfunction "2_2") (pintype "passive"))
    )
    (net (code "190") (name "unconnected-(KH-Pad3)") (class "Default")
      (node (ref "KH") (pin "3") (pinfunction "3_3") (pintype "passive"))
    )
    (net (code "191") (name "unconnected-(KI-Pad2)") (class "Default")
      (node (ref "KI") (pin "2") (pinfunction "2_2") (pintype "passive"))
    )
    (net (code "192") (name "unconnected-(KI-Pad3)") (class "Default")
      (node (ref "KI") (pin "3") (pinfunction "3_3") (pintype "passive"))
    )
    (net (code "193") (name "unconnected-(KJ-Pad2)") (class "Default")
      (node (ref "KJ") (pin "2") (pinfunction "2_2") (pintype "passive"))
    )
    (net (code "194") (name "unconnected-(KJ-Pad3)") (class "Default")
      (node (ref "KJ") (pin "3") (pinfunction "3_3") (pintype "passive"))
    )
    (net (code "195") (name "unconnected-(KK-Pad2)") (class "Default")
      (node (ref "KK") (pin "2") (pinfunction "2_2") (pintype "passive"))
    )
    (net (code "196") (name "unconnected-(KK-Pad3)") (class "Default")
      (node (ref "KK") (pin "3") (pinfunction "3_3") (pintype "passive"))
    )
    (net (code "197") (name "unconnected-(KL-Pad2)") (class "Default")
      (node (ref "KL") (pin "2") (pinfunction "2_2") (pintype "passive"))
    )
    (net (code "198") (name "unconnected-(KL-Pad3)") (class "Default")
      (node (ref "KL") (pin "3") (pinfunction "3_3") (pintype "passive"))
    )
    (net (code "199") (name "unconnected-(KM-Pad2)") (class "Default")
      (node (ref "KM") (pin "2") (pinfunction "2_2") (pintype "passive"))
    )
    (net (code "200") (name "unconnected-(KM-Pad3)") (class "Default")
      (node (ref "KM") (pin "3") (pinfunction "3_3") (pintype "passive"))
    )
    (net (code "201") (name "unconnected-(KN-Pad2)") (class "Default")
      (node (ref "KN") (pin "2") (pinfunction "2_2") (pintype "passive"))
    )
    (net (code "202") (name "unconnected-(KN-Pad3)") (class "Default")
      (node (ref "KN") (pin "3") (pinfunction "3_3") (pintype "passive"))
    )
    (net (code "203") (name "unconnected-(KO-Pad2)") (class "Default")
      (node (ref "KO") (pin "2") (pinfunction "2_2") (pintype "passive"))
    )
    (net (code "204") (name "unconnected-(KO-Pad3)") (class "Default")
      (node (ref "KO") (pin "3") (pinfunction "3_3") (pintype "passive"))
    )
    (net (code "205") (name "unconnected-(KP-Pad2)") (class "Default")
      (node (ref "KP") (pin "2") (pinfunction "2_2") (pintype "passive"))
    )
    (net (code "206") (name "unconnected-(KP-Pad3)") (class "Default")
      (node (ref "KP") (pin "3") (pinfunction "3_3") (pintype "passive"))
    )
    (net (code "207") (name "unconnected-(KQ-Pad2)") (class "Default")
      (node (ref "KQ") (pin "2") (pinfunction "2_2") (pintype "passive"))
    )
    (net (code "208") (name "unconnected-(KQ-Pad3)") (class "Default")
      (node (ref "KQ") (pin "3") (pinfunction "3_3") (pintype "passive"))
    )
    (net (code "209") (name "unconnected-(KR-Pad2)") (class "Default")
      (node (ref "KR") (pin "2") (pinfunction "2_2") (pintype "passive"))
    )
    (net (code "210") (name "unconnected-(KR-Pad3)") (class "Default")
      (node (ref "KR") (pin "3") (pinfunction "3_3") (pintype "passive"))
    )
    (net (code "211") (name "unconnected-(KS-Pad2)") (class "Default")
      (node (ref "KS") (pin "2") (pinfunction "2_2") (pintype "passive"))
    )
    (net (code "212") (name "unconnected-(KS-Pad3)") (class "Default")
      (node (ref "KS") (pin "3") (pinfunction "3_3") (pintype "passive"))
    )
    (net (code "213") (name "unconnected-(KSPACE-Pad2)") (class "Default")
      (node (ref "KSPACE") (pin "2") (pinfunction "2_2") (pintype "passive"))
    )
    (net (code "214") (name "unconnected-(KSPACE-Pad3)") (class "Default")
      (node (ref "KSPACE") (pin "3") (pinfunction "3_3") (pintype "passive"))
    )
    (net (code "215") (name "unconnected-(KSYM-Pad2)") (class "Default")
      (node (ref "KSYM") (pin "2") (pinfunction "2_2") (pintype "passive"))
    )
    (net (code "216") (name "unconnected-(KSYM-Pad3)") (class "Default")
      (node (ref "KSYM") (pin "3") (pinfunction "3_3") (pintype "passive"))
    )
    (net (code "217") (name "unconnected-(KT-Pad2)") (class "Default")
      (node (ref "KT") (pin "2") (pinfunction "2_2") (pintype "passive"))
    )
    (net (code "218") (name "unconnected-(KT-Pad3)") (class "Default")
      (node (ref "KT") (pin "3") (pinfunction "3_3") (pintype "passive"))
    )
    (net (code "219") (name "unconnected-(KU-Pad2)") (class "Default")
      (node (ref "KU") (pin "2") (pinfunction "2_2") (pintype "passive"))
    )
    (net (code "220") (name "unconnected-(KU-Pad3)") (class "Default")
      (node (ref "KU") (pin "3") (pinfunction "3_3") (pintype "passive"))
    )
    (net (code "221") (name "unconnected-(KV-Pad2)") (class "Default")
      (node (ref "KV") (pin "2") (pinfunction "2_2") (pintype "passive"))
    )
    (net (code "222") (name "unconnected-(KV-Pad3)") (class "Default")
      (node (ref "KV") (pin "3") (pinfunction "3_3") (pintype "passive"))
    )
    (net (code "223") (name "unconnected-(KW-Pad2)") (class "Default")
      (node (ref "KW") (pin "2") (pinfunction "2_2") (pintype "passive"))
    )
    (net (code "224") (name "unconnected-(KW-Pad3)") (class "Default")
      (node (ref "KW") (pin "3") (pinfunction "3_3") (pintype "passive"))
    )
    (net (code "225") (name "unconnected-(KX-Pad2)") (class "Default")
      (node (ref "KX") (pin "2") (pinfunction "2_2") (pintype "passive"))
    )
    (net (code "226") (name "unconnected-(KX-Pad3)") (class "Default")
      (node (ref "KX") (pin "3") (pinfunction "3_3") (pintype "passive"))
    )
    (net (code "227") (name "unconnected-(KY-Pad2)") (class "Default")
      (node (ref "KY") (pin "2") (pinfunction "2_2") (pintype "passive"))
    )
    (net (code "228") (name "unconnected-(KY-Pad3)") (class "Default")
      (node (ref "KY") (pin "3") (pinfunction "3_3") (pintype "passive"))
    )
    (net (code "229") (name "unconnected-(KZ-Pad2)") (class "Default")
      (node (ref "KZ") (pin "2") (pinfunction "2_2") (pintype "passive"))
    )
    (net (code "230") (name "unconnected-(KZ-Pad3)") (class "Default")
      (node (ref "KZ") (pin "3") (pinfunction "3_3") (pintype "passive"))
    )
    (net (code "231") (name "unconnected-(U$1-D7-Pad9)") (class "Default")
      (node (ref "U$1") (pin "9") (pinfunction "D7_9") (pintype "bidirectional"))
    )
    (net (code "232") (name "unconnected-(U$1-Q7-Pad12)") (class "Default")
      (node (ref "U$1") (pin "12") (pinfunction "Q7_12") (pintype "bidirectional"))
    )
    (net (code "233") (name "unconnected-(U$2-CHA_OUTPUT-Pad11)") (class "Default")
      (node (ref "U$2") (pin "11") (pinfunction "CHA_OUTPUT_11") (pintype "bidirectional"))
    )
    (net (code "234") (name "unconnected-(U$2-CHA_TANK0-Pad8)") (class "Default")
      (node (ref "U$2") (pin "8") (pinfunction "CHA_TANK0_8") (pintype "bidirectional"))
    )
    (net (code "235") (name "unconnected-(U$2-CHA_TANK1-Pad9)") (class "Default")
      (node (ref "U$2") (pin "9") (pinfunction "CHA_TANK1_9") (pintype "bidirectional"))
    )
    (net (code "236") (name "unconnected-(U$2-CHB_OUTPUT-Pad10)") (class "Default")
      (node (ref "U$2") (pin "10") (pinfunction "CHB_OUTPUT_10") (pintype "bidirectional"))
    )
    (net (code "237") (name "unconnected-(U$2-CHB_TANK0-Pad6)") (class "Default")
      (node (ref "U$2") (pin "6") (pinfunction "CHB_TANK0_6") (pintype "bidirectional"))
    )
    (net (code "238") (name "unconnected-(U$2-CHB_TANK1-Pad7)") (class "Default")
      (node (ref "U$2") (pin "7") (pinfunction "CHB_TANK1_7") (pintype "bidirectional"))
    )
    (net (code "239") (name "unconnected-(U$3-O-Pad1)") (class "Default")
      (node (ref "U$3") (pin "1") (pinfunction "O_1") (pintype "passive"))
    )
    (net (code "240") (name "unconnected-(U$3-P-Pad2)") (class "Default")
      (node (ref "U$3") (pin "2") (pinfunction "P_2") (pintype "passive"))
    )
    (net (code "241") (name "unconnected-(Z80A-BUSAK-Pad23)") (class "Default")
      (node (ref "Z80A") (pin "23") (pinfunction "BUSAK_23") (pintype "output"))
    )
    (net (code "242") (name "unconnected-(Z80A-HALT-Pad18)") (class "Default")
      (node (ref "Z80A") (pin "18") (pinfunction "HALT_18") (pintype "output"))
    )
    (net (code "243") (name "unconnected-(Z80A-M1-Pad27)") (class "Default")
      (node (ref "Z80A") (pin "27") (pinfunction "M1_27") (pintype "output"))
    )
    (net (code "244") (name "unconnected-(Z80A-RFSH-Pad28)") (class "Default")
      (node (ref "Z80A") (pin "28") (pinfunction "RFSH_28") (pintype "output"))
    )
  )
)
